# Reach_B0.net
KiCad netlist of a schematic drawn in EAGLE
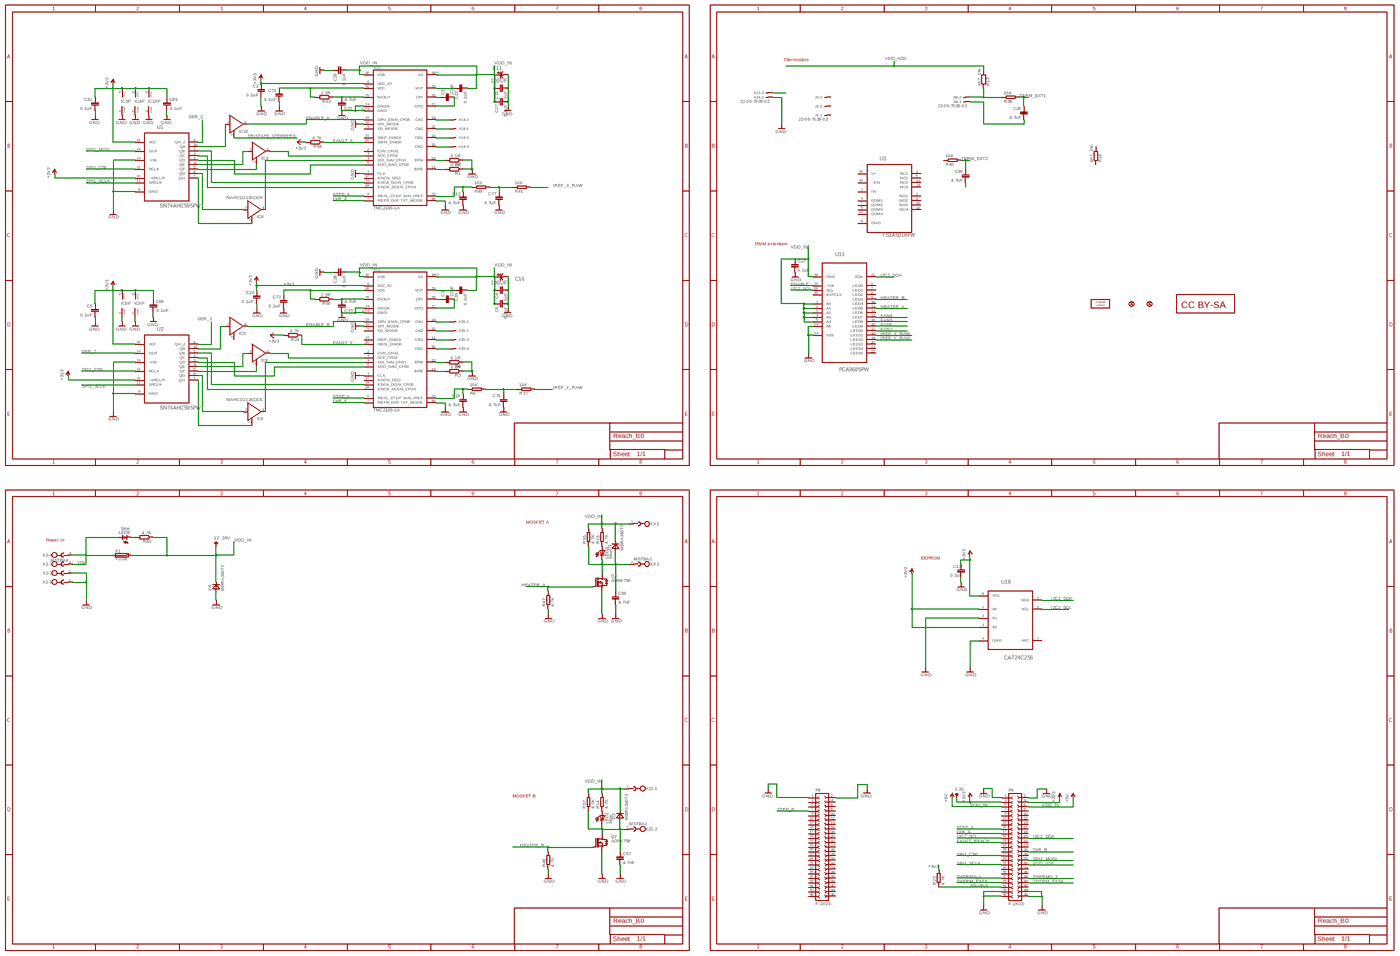
[diagram p0: schematic, sheet 1, overview]
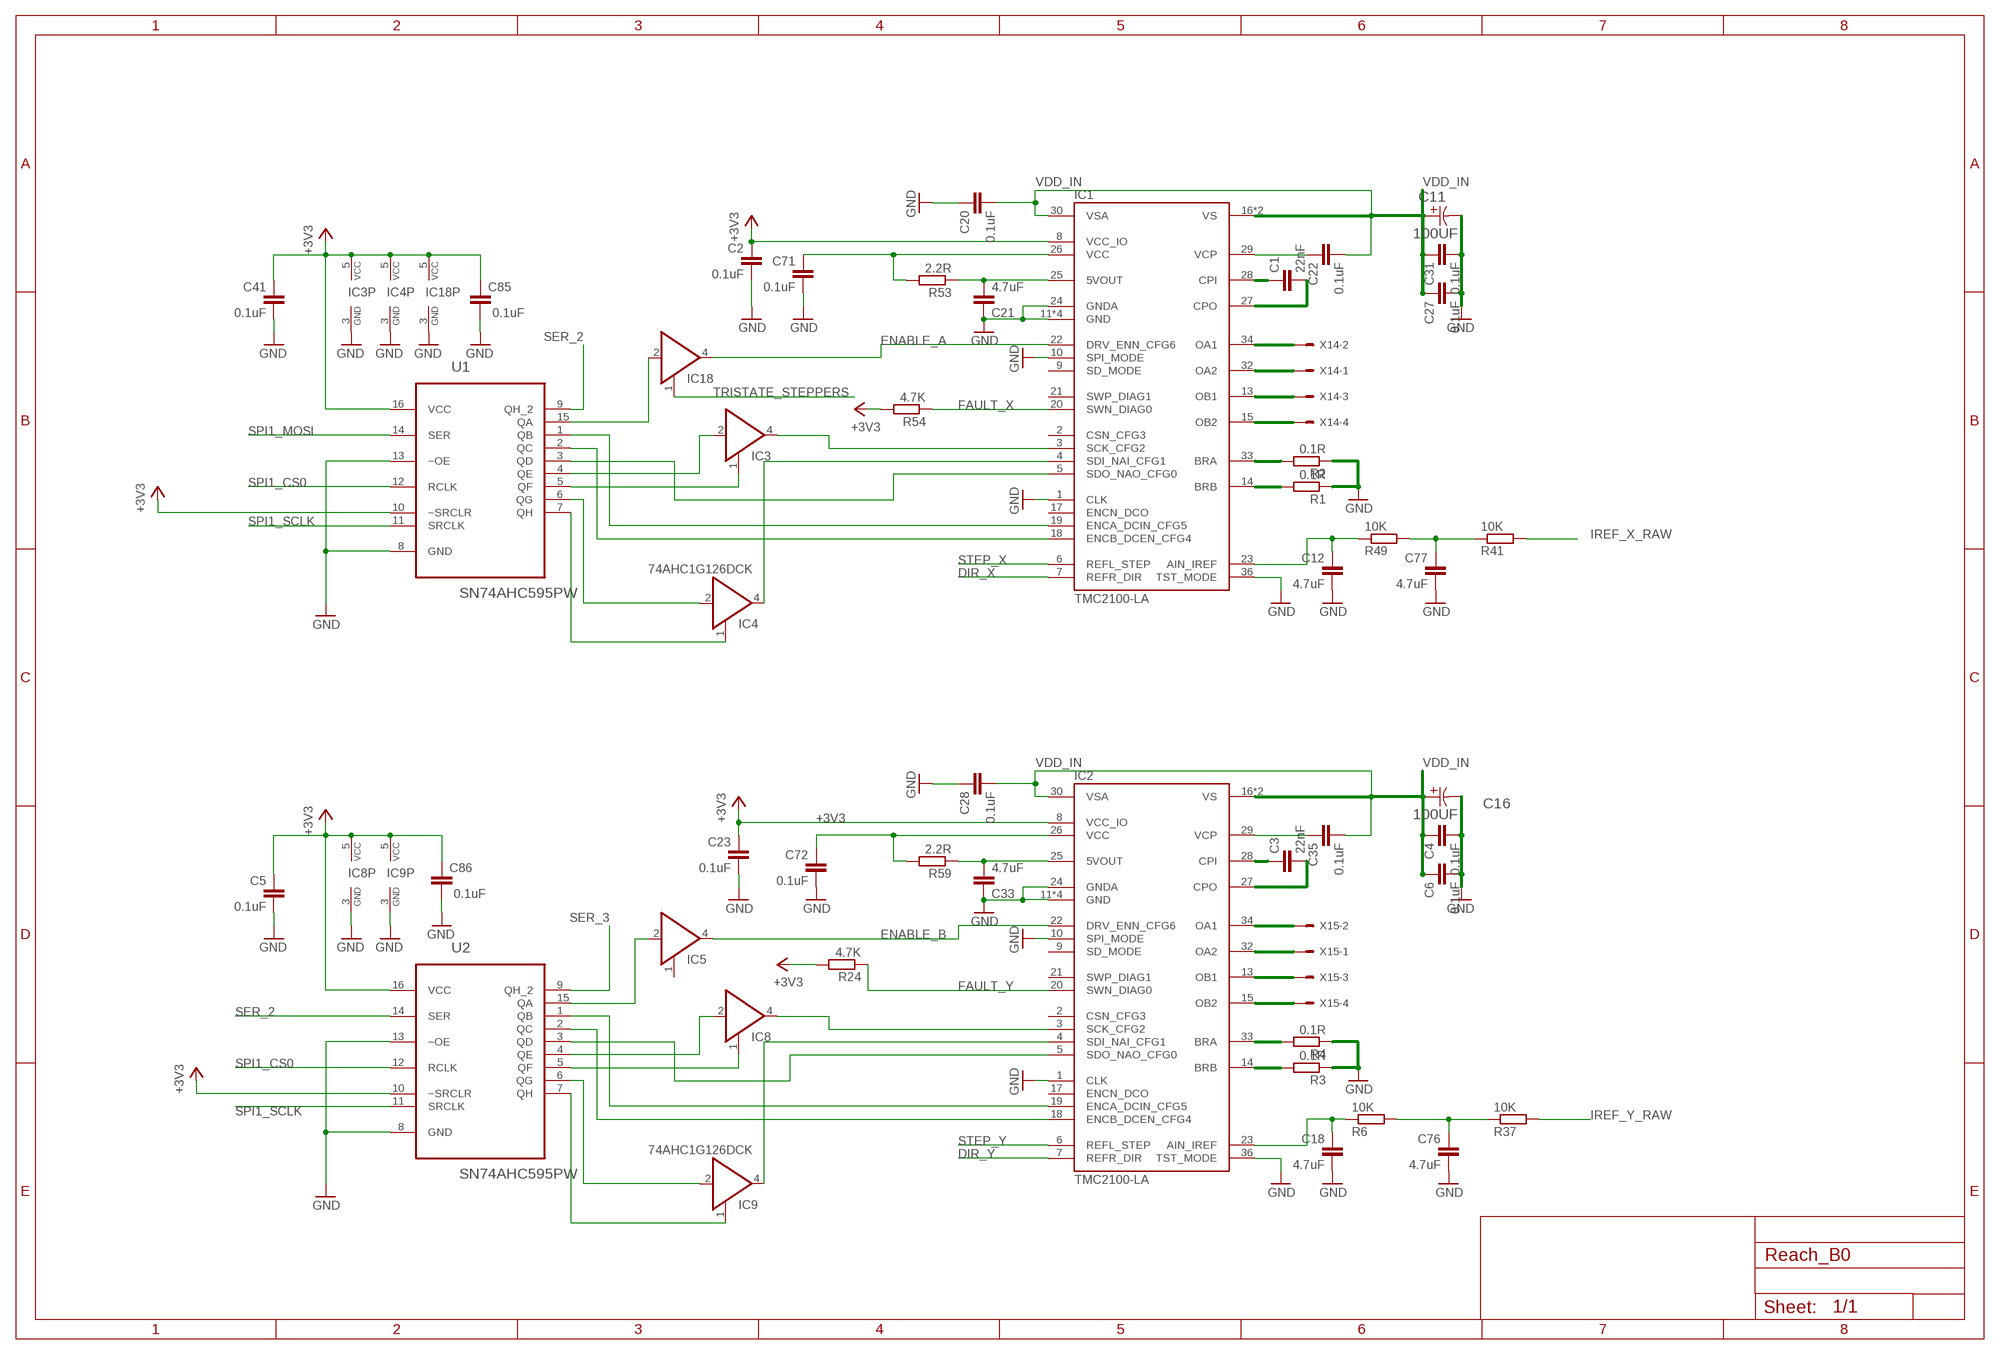
[diagram p1: schematic, sheet 1, part 1 of 4]
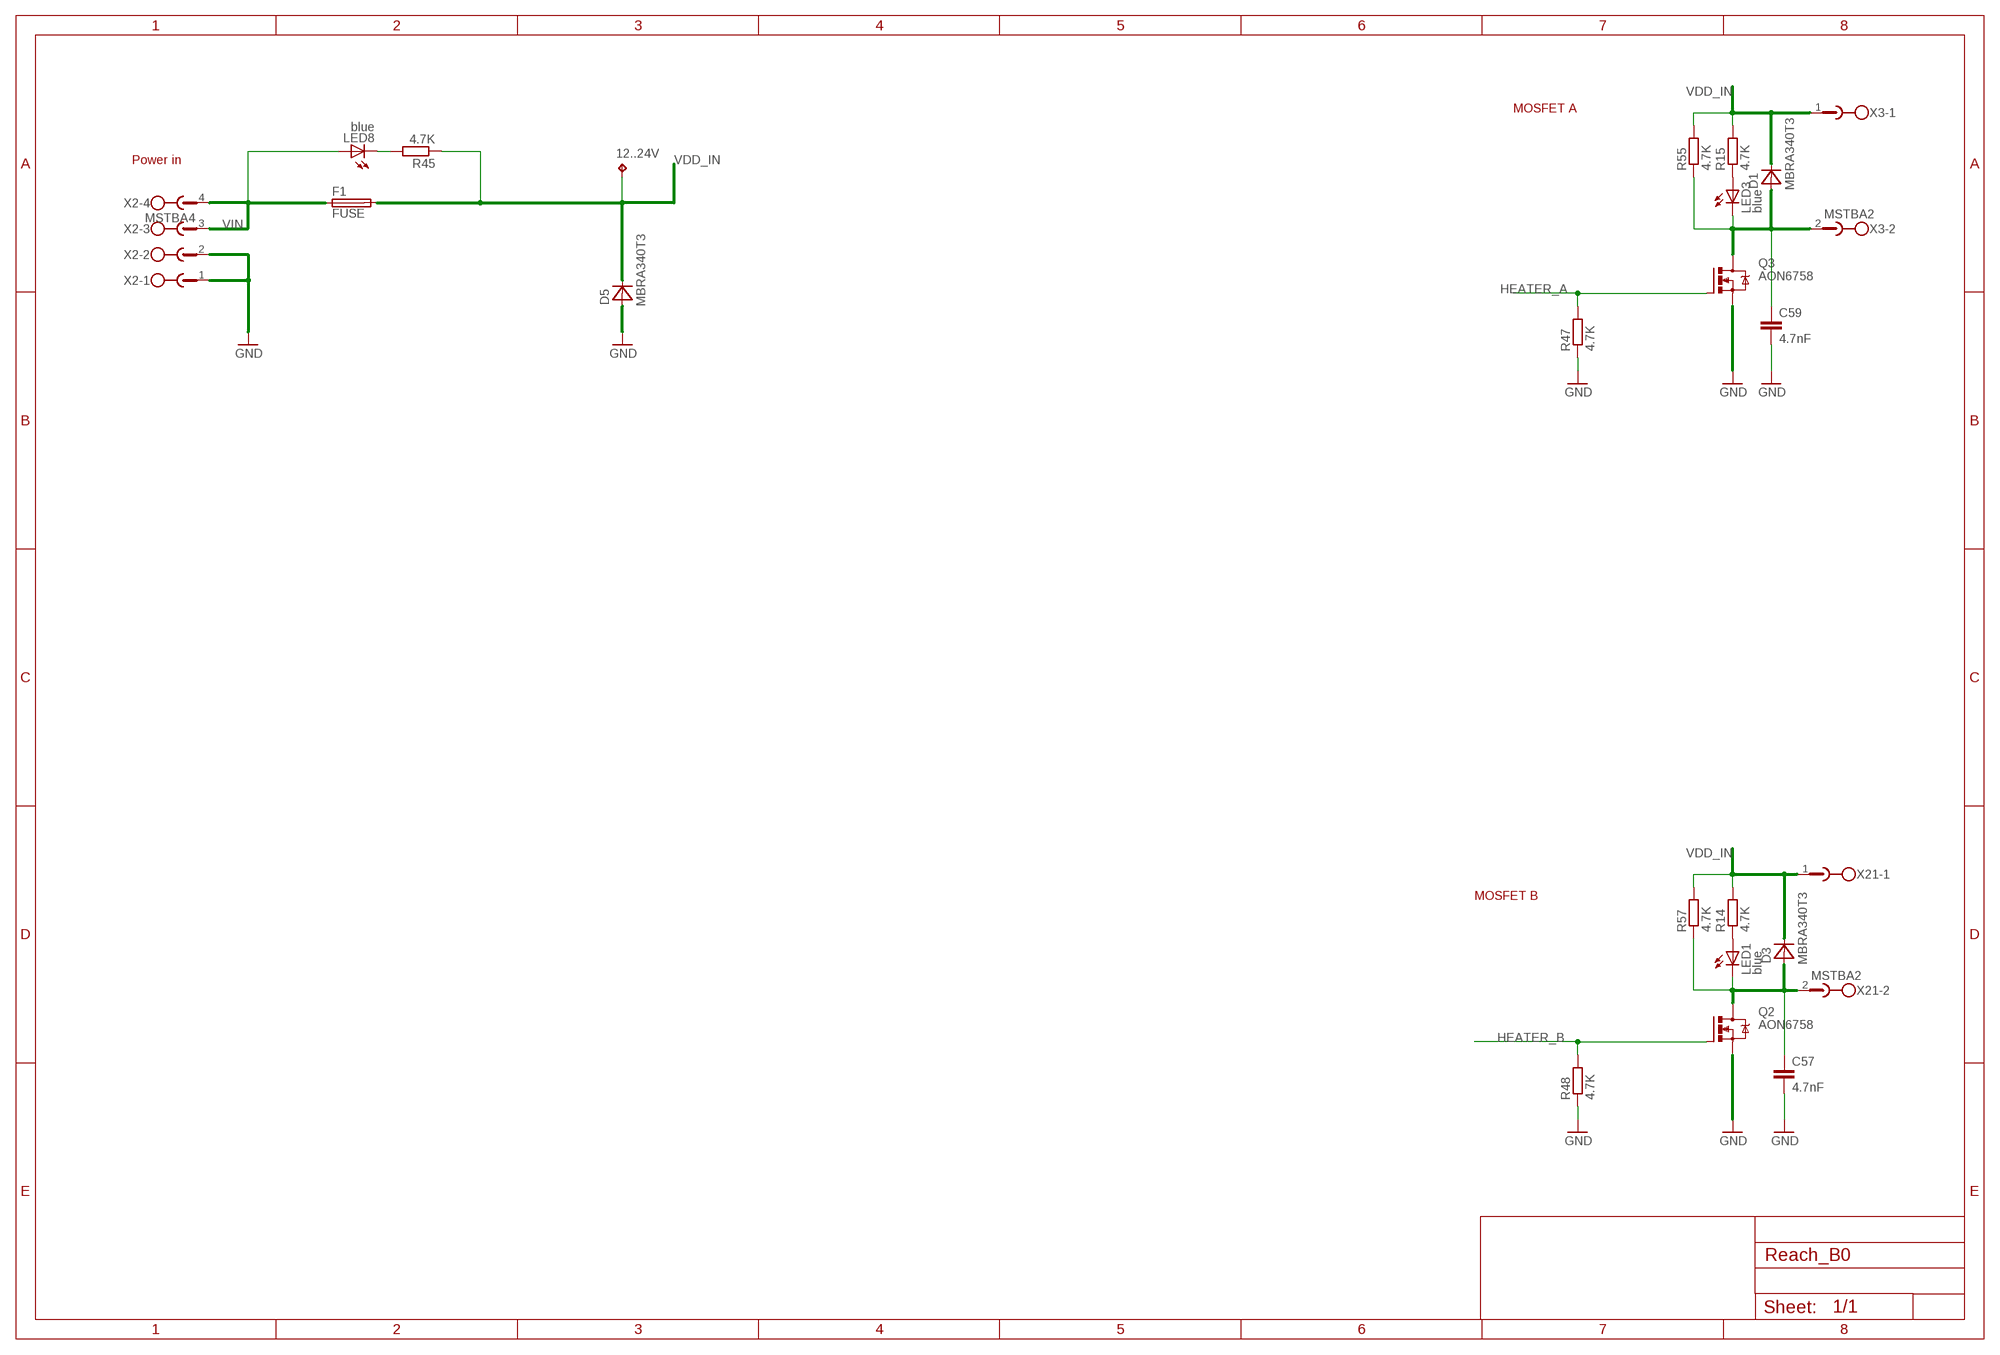
[diagram p2: schematic, sheet 1, part 2 of 4]
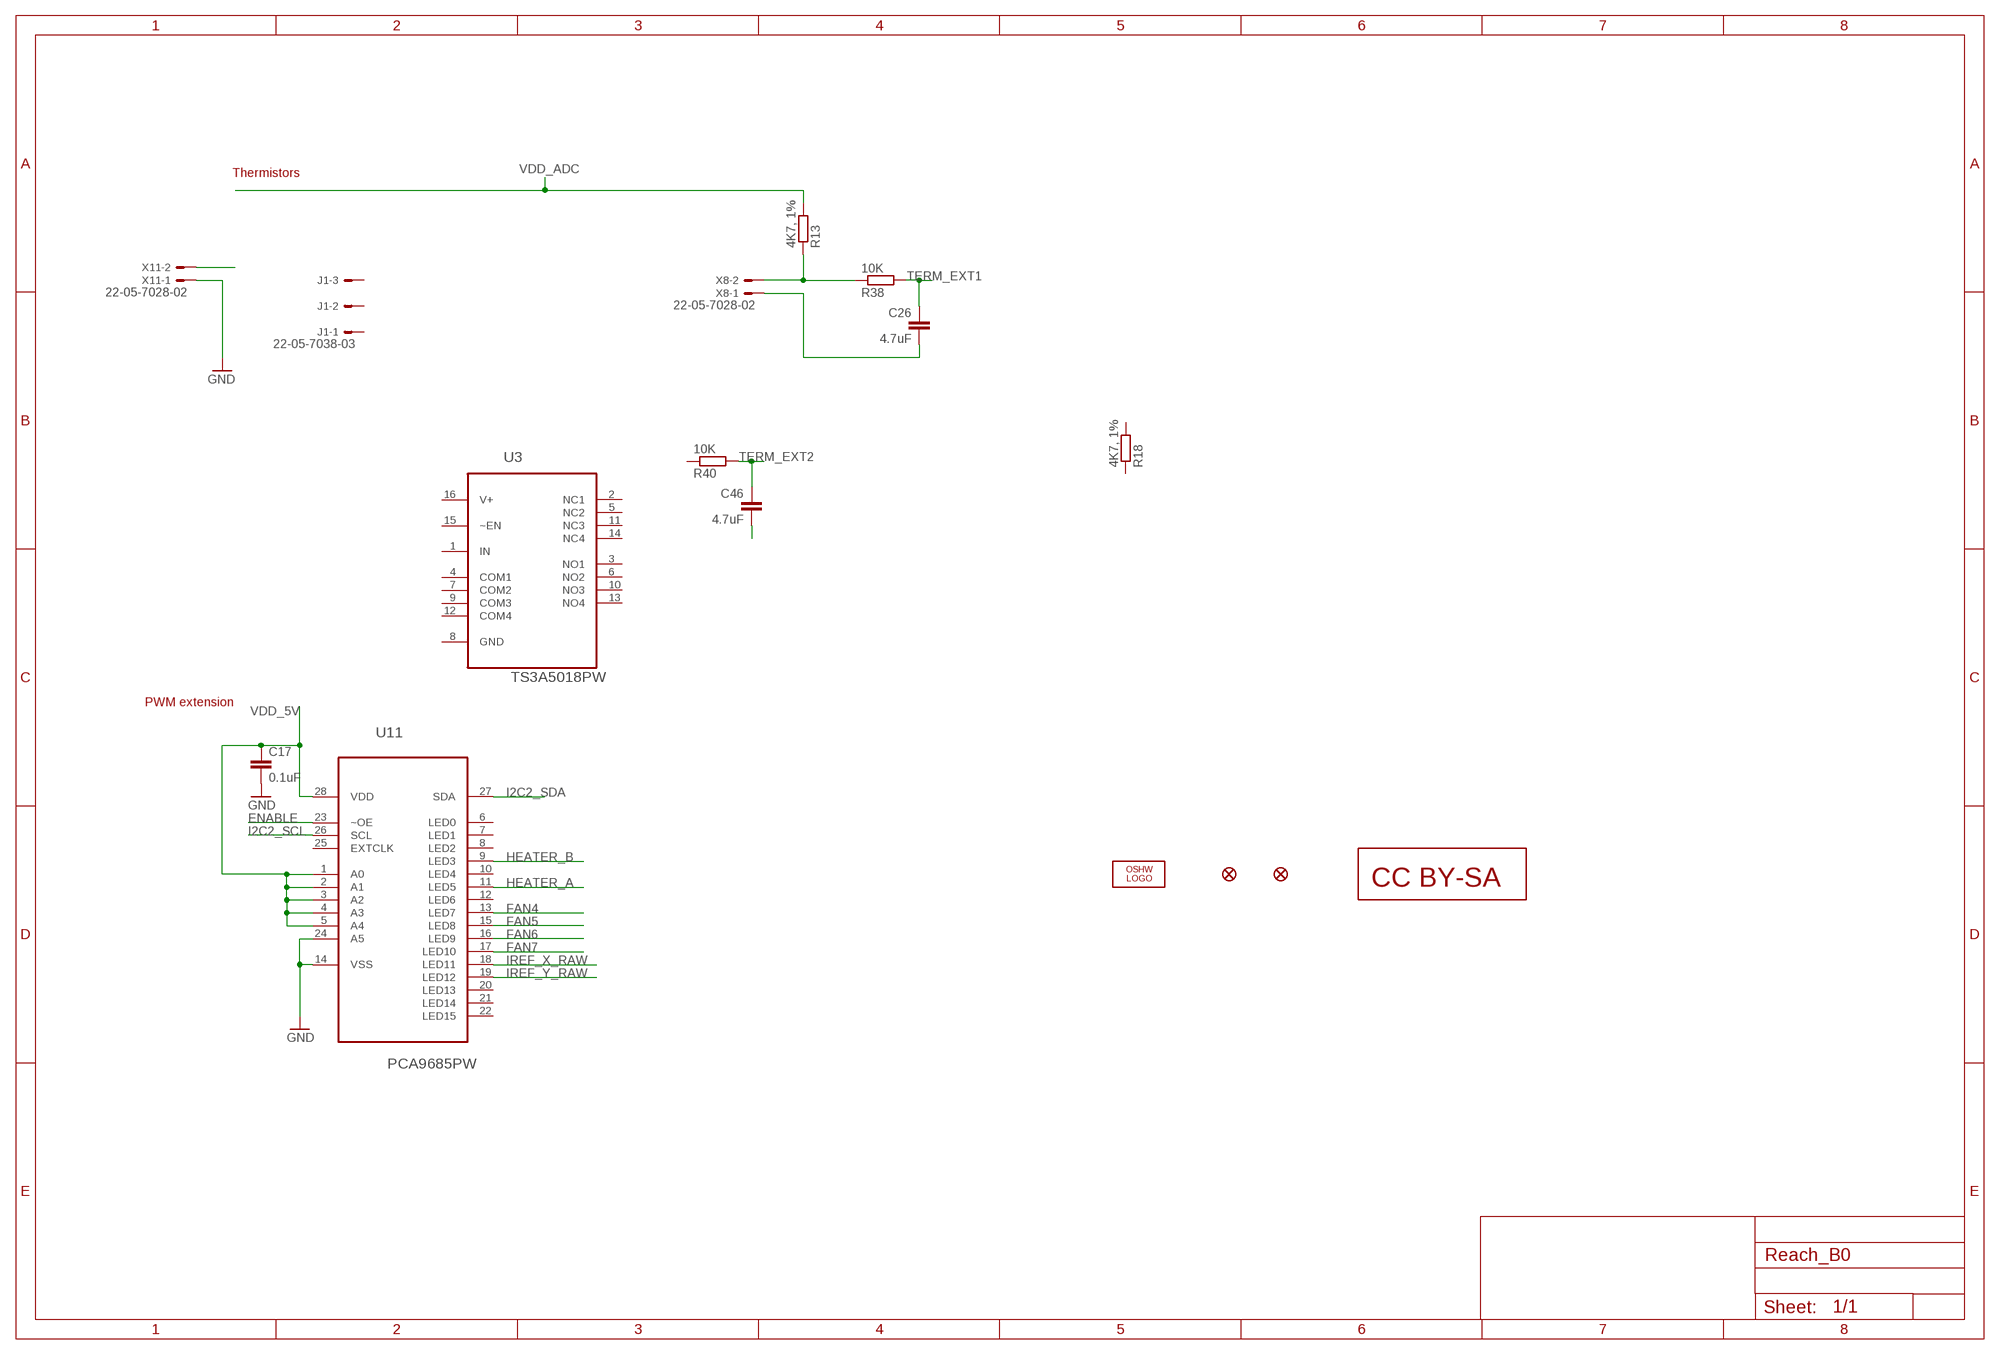
[diagram p3: schematic, sheet 1, part 3 of 4]
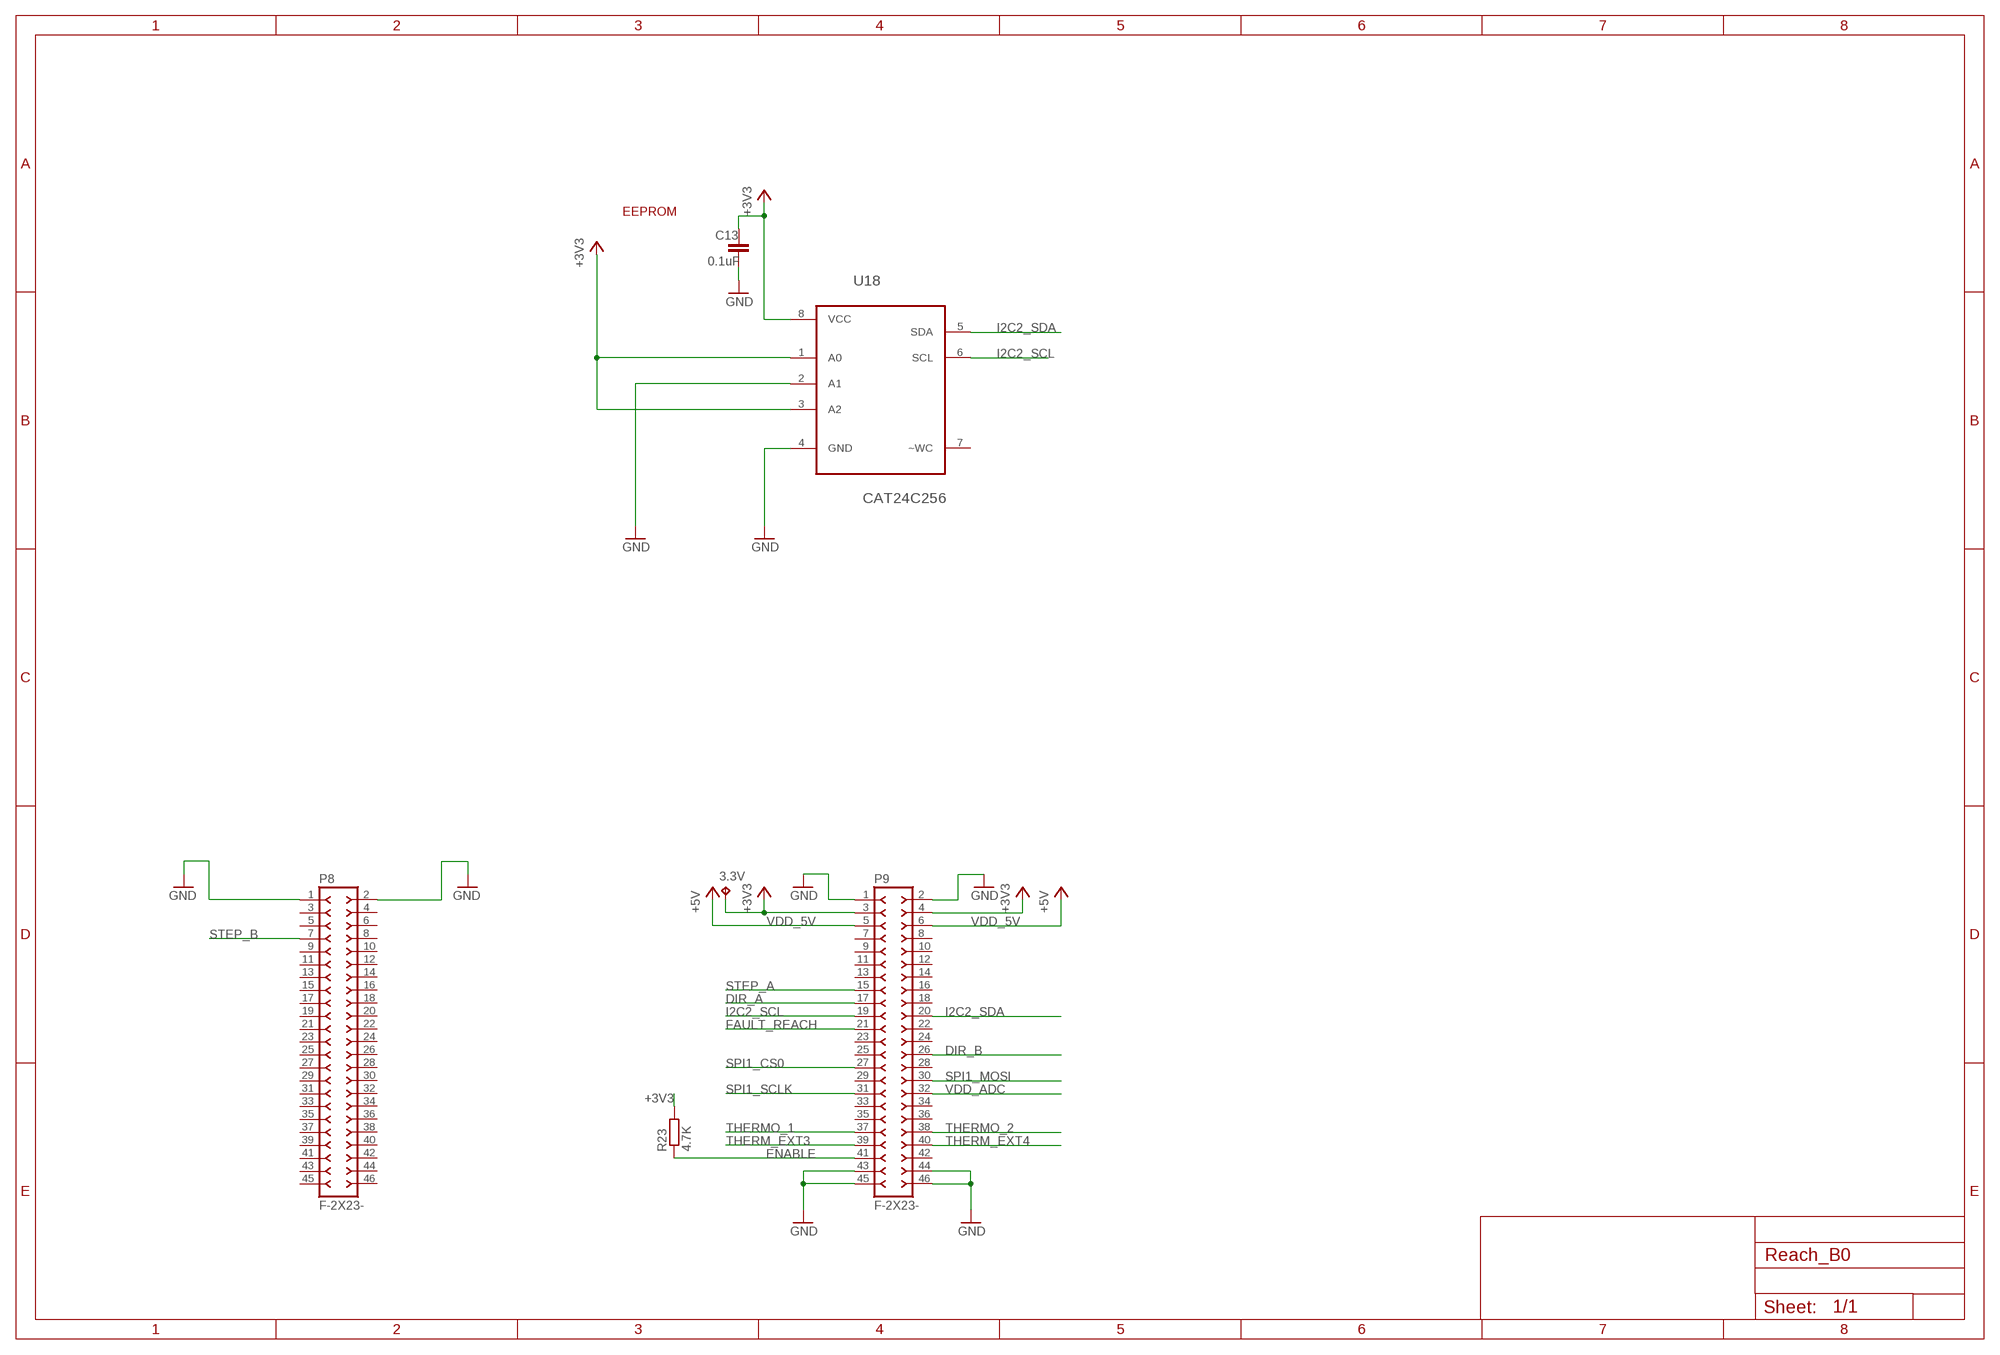
[diagram p4: schematic, sheet 1, part 4 of 4]

(export (version "E")
  (design (tool "Eeschema 10.0.6"))
  (components
    (comp (ref "3.3V")
      (value "TPB1,27")
      (footprint "eagle-import:B1,27")
      (libsource (lib "eagle-import") (part "TPB1,27"))
    )
    (comp (ref "12..24V")
      (value "TPB1,27")
      (footprint "eagle-import:B1,27")
      (libsource (lib "eagle-import") (part "TPB1,27"))
    )
    (comp (ref "C1")
      (value "22nF")
      (footprint "eagle-import:C0402")
      (libsource (lib "eagle-import") (part "C-EUC0402"))
    )
    (comp (ref "C2")
      (value "0.1uF")
      (footprint "eagle-import:C0402")
      (libsource (lib "eagle-import") (part "C-EUC0402"))
    )
    (comp (ref "C3")
      (value "22nF")
      (footprint "eagle-import:C0402")
      (libsource (lib "eagle-import") (part "C-EUC0402"))
    )
    (comp (ref "C4")
      (value "0.1uF")
      (footprint "eagle-import:C0402")
      (libsource (lib "eagle-import") (part "C-EUC0402"))
    )
    (comp (ref "C5")
      (value "0.1uF")
      (footprint "eagle-import:C0402")
      (libsource (lib "eagle-import") (part "C-EUC0402"))
    )
    (comp (ref "C6")
      (value "0.1uF")
      (footprint "eagle-import:C0402")
      (libsource (lib "eagle-import") (part "C-EUC0402"))
    )
    (comp (ref "C11")
      (value "100UF")
      (footprint "eagle-import:CAPAE660X800N")
      (fields (field (name "MPN") "EEE-FK1V101XP") (field (name "TOLERANCE") "±20 %"))
      (libsource (lib "eagle-import") (part "EEE--CASE-D8FK1V101XP"))
    )
    (comp (ref "C12")
      (value "4.7uF")
      (footprint "eagle-import:C0402")
      (libsource (lib "eagle-import") (part "C-EUC0402"))
    )
    (comp (ref "C13")
      (value "0.1uF")
      (footprint "eagle-import:C0402")
      (libsource (lib "eagle-import") (part "C-EUC0402"))
    )
    (comp (ref "C16")
      (value "100UF")
      (footprint "eagle-import:CAPAE660X800N")
      (fields (field (name "MPN") "EEE-FK1V101XP") (field (name "TOLERANCE") "±20 %"))
      (libsource (lib "eagle-import") (part "EEE--CASE-D8FK1V101XP"))
    )
    (comp (ref "C17")
      (value "0.1uF")
      (footprint "eagle-import:C0402")
      (libsource (lib "eagle-import") (part "C-EUC0402"))
    )
    (comp (ref "C18")
      (value "4.7uF")
      (footprint "eagle-import:C0402")
      (libsource (lib "eagle-import") (part "C-EUC0402"))
    )
    (comp (ref "C20")
      (value "0.1uF")
      (footprint "eagle-import:C0402")
      (libsource (lib "eagle-import") (part "C-EUC0402"))
    )
    (comp (ref "C21")
      (value "4.7uF")
      (footprint "eagle-import:C0402")
      (libsource (lib "eagle-import") (part "C-EUC0402"))
    )
    (comp (ref "C22")
      (value "0.1uF")
      (footprint "eagle-import:C0402")
      (libsource (lib "eagle-import") (part "C-EUC0402"))
    )
    (comp (ref "C23")
      (value "0.1uF")
      (footprint "eagle-import:C0402")
      (libsource (lib "eagle-import") (part "C-EUC0402"))
    )
    (comp (ref "C26")
      (value "4.7uF")
      (footprint "eagle-import:C0402")
      (libsource (lib "eagle-import") (part "C-EUC0402"))
    )
    (comp (ref "C27")
      (value "0.1uF")
      (footprint "eagle-import:C0402")
      (libsource (lib "eagle-import") (part "C-EUC0402"))
    )
    (comp (ref "C28")
      (value "0.1uF")
      (footprint "eagle-import:C0402")
      (libsource (lib "eagle-import") (part "C-EUC0402"))
    )
    (comp (ref "C31")
      (value "0.1uF")
      (footprint "eagle-import:C0402")
      (libsource (lib "eagle-import") (part "C-EUC0402"))
    )
    (comp (ref "C33")
      (value "4.7uF")
      (footprint "eagle-import:C0402")
      (libsource (lib "eagle-import") (part "C-EUC0402"))
    )
    (comp (ref "C35")
      (value "0.1uF")
      (footprint "eagle-import:C0402")
      (libsource (lib "eagle-import") (part "C-EUC0402"))
    )
    (comp (ref "C41")
      (value "0.1uF")
      (footprint "eagle-import:C0402")
      (libsource (lib "eagle-import") (part "C-EUC0402"))
    )
    (comp (ref "C46")
      (value "4.7uF")
      (footprint "eagle-import:C0402")
      (libsource (lib "eagle-import") (part "C-EUC0402"))
    )
    (comp (ref "C57")
      (value "4.7nF")
      (footprint "eagle-import:C0402")
      (libsource (lib "eagle-import") (part "C-EUC0402"))
    )
    (comp (ref "C59")
      (value "4.7nF")
      (footprint "eagle-import:C0402")
      (libsource (lib "eagle-import") (part "C-EUC0402"))
    )
    (comp (ref "C71")
      (value "0.1uF")
      (footprint "eagle-import:C0402")
      (libsource (lib "eagle-import") (part "C-EUC0402"))
    )
    (comp (ref "C72")
      (value "0.1uF")
      (footprint "eagle-import:C0402")
      (libsource (lib "eagle-import") (part "C-EUC0402"))
    )
    (comp (ref "C76")
      (value "4.7uF")
      (footprint "eagle-import:C0402")
      (libsource (lib "eagle-import") (part "C-EUC0402"))
    )
    (comp (ref "C77")
      (value "4.7uF")
      (footprint "eagle-import:C0402")
      (libsource (lib "eagle-import") (part "C-EUC0402"))
    )
    (comp (ref "C85")
      (value "0.1uF")
      (footprint "eagle-import:C0402")
      (libsource (lib "eagle-import") (part "C-EUC0402"))
    )
    (comp (ref "C86")
      (value "0.1uF")
      (footprint "eagle-import:C0402")
      (libsource (lib "eagle-import") (part "C-EUC0402"))
    )
    (comp (ref "D1")
      (value "MBRA340T3")
      (footprint "eagle-import:SMA")
      (libsource (lib "eagle-import") (part "MBRA340T3"))
    )
    (comp (ref "D3")
      (value "MBRA340T3")
      (footprint "eagle-import:SMA")
      (libsource (lib "eagle-import") (part "MBRA340T3"))
    )
    (comp (ref "D5")
      (value "MBRA340T3")
      (footprint "eagle-import:SMA")
      (libsource (lib "eagle-import") (part "MBRA340T3"))
    )
    (comp (ref "F1")
      (value "FUSE")
      (footprint "eagle-import:3557")
      (libsource (lib "eagle-import") (part "FUSE"))
    )
    (comp (ref "IC1")
      (value "TMC2100-LA")
      (footprint "eagle-import:QFN36-PAD")
      (libsource (lib "eagle-import") (part "TMC2100-LA"))
    )
    (comp (ref "IC2")
      (value "TMC2100-LA")
      (footprint "eagle-import:QFN36-PAD")
      (libsource (lib "eagle-import") (part "TMC2100-LA"))
    )
    (comp (ref "IC3")
      (value "74AHC1G126DCK")
      (footprint "eagle-import:SC70-5")
      (libsource (lib "eagle-import") (part "741G126DCKAHC"))
    )
    (comp (ref "IC4")
      (value "74AHC1G126DCK")
      (footprint "eagle-import:SC70-5")
      (libsource (lib "eagle-import") (part "741G126DCKAHC"))
    )
    (comp (ref "IC5")
      (value "74AHC1G126DCK")
      (footprint "eagle-import:SC70-5")
      (libsource (lib "eagle-import") (part "741G126DCKAHC"))
    )
    (comp (ref "IC8")
      (value "74AHC1G126DCK")
      (footprint "eagle-import:SC70-5")
      (libsource (lib "eagle-import") (part "741G126DCKAHC"))
    )
    (comp (ref "IC9")
      (value "74AHC1G126DCK")
      (footprint "eagle-import:SC70-5")
      (libsource (lib "eagle-import") (part "741G126DCKAHC"))
    )
    (comp (ref "IC18")
      (value "74AHC1G126DCK")
      (footprint "eagle-import:SC70-5")
      (libsource (lib "eagle-import") (part "741G126DCKAHC"))
    )
    (comp (ref "J1")
      (value "22-05-7038-03")
      (footprint "eagle-import:7395-03")
      (libsource (lib "eagle-import") (part "22-?-0305-7038"))
    )
    (comp (ref "JP1")
      (value "FIDUCIAL1X2.5")
      (footprint "eagle-import:FIDUCIAL-1X2.5")
      (libsource (lib "eagle-import") (part "FIDUCIAL1X2.5"))
    )
    (comp (ref "JP2")
      (value "FIDUCIAL1X2.5")
      (footprint "eagle-import:FIDUCIAL-1X2.5")
      (libsource (lib "eagle-import") (part "FIDUCIAL1X2.5"))
    )
    (comp (ref "LED1")
      (value "blue")
      (footprint "eagle-import:CHIP-LED0603")
      (libsource (lib "eagle-import") (part "LEDCHIP-LED0603"))
    )
    (comp (ref "LED3")
      (value "blue")
      (footprint "eagle-import:CHIP-LED0603")
      (libsource (lib "eagle-import") (part "LEDCHIP-LED0603"))
    )
    (comp (ref "LED8")
      (value "blue")
      (footprint "eagle-import:CHIP-LED0603")
      (libsource (lib "eagle-import") (part "LEDCHIP-LED0603"))
    )
    (comp (ref "LOGO1")
      (value "OSHW_LOGO_FILLX0200-NT")
      (footprint "eagle-import:OSHW_FILLX200_NOTEXT")
      (libsource (lib "eagle-import") (part "OSHW_LOGO_FILLX0200-NT"))
    )
    (comp (ref "P8")
      (value "F-2X23-")
      (footprint "eagle-import:DIL-100-2X23")
      (libsource (lib "eagle-import") (part "F-2X23-"))
    )
    (comp (ref "P9")
      (value "F-2X23-")
      (footprint "eagle-import:DIL-100-2X23")
      (libsource (lib "eagle-import") (part "F-2X23-"))
    )
    (comp (ref "Q2")
      (value "AON6758")
      (footprint "eagle-import:8-DFN-EP-(5X6)")
      (libsource (lib "eagle-import") (part "AON6758"))
    )
    (comp (ref "Q3")
      (value "AON6758")
      (footprint "eagle-import:8-DFN-EP-(5X6)")
      (libsource (lib "eagle-import") (part "AON6758"))
    )
    (comp (ref "R1")
      (value "0.1R")
      (footprint "eagle-import:R0805")
      (libsource (lib "eagle-import") (part "R-EU_R0805"))
    )
    (comp (ref "R2")
      (value "0.1R")
      (footprint "eagle-import:R0805")
      (libsource (lib "eagle-import") (part "R-EU_R0805"))
    )
    (comp (ref "R3")
      (value "0.1R")
      (footprint "eagle-import:R0805")
      (libsource (lib "eagle-import") (part "R-EU_R0805"))
    )
    (comp (ref "R4")
      (value "0.1R")
      (footprint "eagle-import:R0805")
      (libsource (lib "eagle-import") (part "R-EU_R0805"))
    )
    (comp (ref "R6")
      (value "10K")
      (footprint "eagle-import:R0402")
      (libsource (lib "eagle-import") (part "R-EU_R0402"))
    )
    (comp (ref "R13")
      (value "4K7, 1%")
      (footprint "eagle-import:R0402")
      (libsource (lib "eagle-import") (part "R-EU_R0402"))
    )
    (comp (ref "R14")
      (value "4.7K")
      (footprint "eagle-import:R0402")
      (libsource (lib "eagle-import") (part "R-EU_R0402"))
    )
    (comp (ref "R15")
      (value "4.7K")
      (footprint "eagle-import:R0402")
      (libsource (lib "eagle-import") (part "R-EU_R0402"))
    )
    (comp (ref "R18")
      (value "4K7, 1%")
      (footprint "eagle-import:R0402")
      (libsource (lib "eagle-import") (part "R-EU_R0402"))
    )
    (comp (ref "R23")
      (value "4.7K")
      (footprint "eagle-import:R0402")
      (libsource (lib "eagle-import") (part "R-EU_R0402"))
    )
    (comp (ref "R24")
      (value "4.7K")
      (footprint "eagle-import:R0402")
      (libsource (lib "eagle-import") (part "R-EU_R0402"))
    )
    (comp (ref "R37")
      (value "10K")
      (footprint "eagle-import:R0402")
      (libsource (lib "eagle-import") (part "R-EU_R0402"))
    )
    (comp (ref "R38")
      (value "10K")
      (footprint "eagle-import:R0402")
      (libsource (lib "eagle-import") (part "R-EU_R0402"))
    )
    (comp (ref "R40")
      (value "10K")
      (footprint "eagle-import:R0402")
      (libsource (lib "eagle-import") (part "R-EU_R0402"))
    )
    (comp (ref "R41")
      (value "10K")
      (footprint "eagle-import:R0402")
      (libsource (lib "eagle-import") (part "R-EU_R0402"))
    )
    (comp (ref "R45")
      (value "4.7K")
      (footprint "eagle-import:R0402")
      (libsource (lib "eagle-import") (part "R-EU_R0402"))
    )
    (comp (ref "R47")
      (value "4.7K")
      (footprint "eagle-import:R0402")
      (libsource (lib "eagle-import") (part "R-EU_R0402"))
    )
    (comp (ref "R48")
      (value "4.7K")
      (footprint "eagle-import:R0402")
      (libsource (lib "eagle-import") (part "R-EU_R0402"))
    )
    (comp (ref "R49")
      (value "10K")
      (footprint "eagle-import:R0402")
      (libsource (lib "eagle-import") (part "R-EU_R0402"))
    )
    (comp (ref "R53")
      (value "2.2R")
      (footprint "eagle-import:R0402")
      (libsource (lib "eagle-import") (part "R-EU_R0402"))
    )
    (comp (ref "R54")
      (value "4.7K")
      (footprint "eagle-import:R0402")
      (libsource (lib "eagle-import") (part "R-EU_R0402"))
    )
    (comp (ref "R55")
      (value "4.7K")
      (footprint "eagle-import:R0402")
      (libsource (lib "eagle-import") (part "R-EU_R0402"))
    )
    (comp (ref "R57")
      (value "4.7K")
      (footprint "eagle-import:R0402")
      (libsource (lib "eagle-import") (part "R-EU_R0402"))
    )
    (comp (ref "R59")
      (value "2.2R")
      (footprint "eagle-import:R0402")
      (libsource (lib "eagle-import") (part "R-EU_R0402"))
    )
    (comp (ref "U$4")
      (value "CC-BY-SA")
      (footprint "eagle-import:CC-BY-SA")
      (libsource (lib "eagle-import") (part "CC-BY-SA"))
    )
    (comp (ref "U1")
      (value "SN74AHC595PW")
      (footprint "eagle-import:SOP65P640X120-16N")
      (libsource (lib "eagle-import") (part "SN74AHC595PW"))
    )
    (comp (ref "U2")
      (value "SN74AHC595PW")
      (footprint "eagle-import:SOP65P640X120-16N")
      (libsource (lib "eagle-import") (part "SN74AHC595PW"))
    )
    (comp (ref "U3")
      (value "TS3A5018PW")
      (footprint "eagle-import:SOP65P640X120-16N")
      (libsource (lib "eagle-import") (part "TS3A5018PW"))
    )
    (comp (ref "U11")
      (value "PCA9685PW")
      (footprint "eagle-import:SOP65P640X110-28N")
      (libsource (lib "eagle-import") (part "PCA9685PW"))
    )
    (comp (ref "U18")
      (value "CAT24C256")
      (footprint "eagle-import:SOIC127P600X175-8N")
      (libsource (lib "eagle-import") (part "CAT24C256"))
    )
    (comp (ref "X2")
      (value "MSTBA4")
      (footprint "eagle-import:MSTBA4")
      (fields (field (name "MF") "FARNELL") (field (name "MPN") "1757268"))
      (libsource (lib "eagle-import") (part "MSTBA4"))
    )
    (comp (ref "X3")
      (value "MSTBA2")
      (footprint "eagle-import:MSTBA2")
      (fields (field (name "MF") "FARNELL") (field (name "MPN") "1757242"))
      (libsource (lib "eagle-import") (part "MSTBA2"))
    )
    (comp (ref "X8")
      (value "22-05-7028-02")
      (footprint "eagle-import:7395-02")
      (libsource (lib "eagle-import") (part "22-?-0205-7028"))
    )
    (comp (ref "X11")
      (value "22-05-7028-02")
      (footprint "eagle-import:7395-02")
      (libsource (lib "eagle-import") (part "22-?-0205-7028"))
    )
    (comp (ref "X14")
      (value "22-05-7048-04")
      (footprint "eagle-import:7395-04")
      (libsource (lib "eagle-import") (part "22-?-0405-7048"))
    )
    (comp (ref "X15")
      (value "22-05-7048-04")
      (footprint "eagle-import:7395-04")
      (libsource (lib "eagle-import") (part "22-?-0405-7048"))
    )
    (comp (ref "X21")
      (value "MSTBA2")
      (footprint "eagle-import:MSTBA2")
      (fields (field (name "MF") "FARNELL") (field (name "MPN") "1757242"))
      (libsource (lib "eagle-import") (part "MSTBA2"))
    )
  )
  (nets
    (net (code "1") (name "+3V3") (class "Default")
      (node (ref "3.3V") (pin "TP") (pinfunction "TP_TP") (pintype "input"))
      (node (ref "C13") (pin "1") (pinfunction "1_1") (pintype "passive"))
      (node (ref "C2") (pin "1") (pinfunction "1_1") (pintype "passive"))
      (node (ref "C23") (pin "1") (pinfunction "1_1") (pintype "passive"))
      (node (ref "C41") (pin "1") (pinfunction "1_1") (pintype "passive"))
      (node (ref "C5") (pin "1") (pinfunction "1_1") (pintype "passive"))
      (node (ref "C85") (pin "1") (pinfunction "1_1") (pintype "passive"))
      (node (ref "C86") (pin "1") (pinfunction "1_1") (pintype "passive"))
      (node (ref "IC1") (pin "8") (pinfunction "VCC_IO_8") (pintype "bidirectional"))
      (node (ref "IC18") (pin "5") (pinfunction "VCC_5") (pintype "power_in"))
      (node (ref "IC2") (pin "8") (pinfunction "VCC_IO_8") (pintype "bidirectional"))
      (node (ref "IC3") (pin "5") (pinfunction "VCC_5") (pintype "power_in"))
      (node (ref "IC4") (pin "5") (pinfunction "VCC_5") (pintype "power_in"))
      (node (ref "IC8") (pin "5") (pinfunction "VCC_5") (pintype "power_in"))
      (node (ref "IC9") (pin "5") (pinfunction "VCC_5") (pintype "power_in"))
      (node (ref "P9") (pin "3") (pinfunction "3_3") (pintype "passive"))
      (node (ref "P9") (pin "4") (pinfunction "4_4") (pintype "passive"))
      (node (ref "R23") (pin "2") (pinfunction "2_2") (pintype "passive"))
      (node (ref "R24") (pin "2") (pinfunction "2_2") (pintype "passive"))
      (node (ref "R54") (pin "2") (pinfunction "2_2") (pintype "passive"))
      (node (ref "U1") (pin "10") (pinfunction "~{SRCLR}_10") (pintype "input"))
      (node (ref "U1") (pin "16") (pinfunction "VCC_16") (pintype "power_in"))
      (node (ref "U18") (pin "1") (pinfunction "A0_1") (pintype "input"))
      (node (ref "U18") (pin "3") (pinfunction "A2_3") (pintype "input"))
      (node (ref "U18") (pin "8") (pinfunction "VCC_8") (pintype "power_in"))
      (node (ref "U2") (pin "10") (pinfunction "~{SRCLR}_10") (pintype "input"))
      (node (ref "U2") (pin "16") (pinfunction "VCC_16") (pintype "power_in"))
    )
    (net (code "2") (name "+5V") (class "Default")
      (node (ref "C17") (pin "1") (pinfunction "1_1") (pintype "passive"))
      (node (ref "P9") (pin "5") (pinfunction "5_5") (pintype "passive"))
      (node (ref "P9") (pin "6") (pinfunction "6_6") (pintype "passive"))
      (node (ref "U11") (pin "1") (pinfunction "A0_1") (pintype "input"))
      (node (ref "U11") (pin "2") (pinfunction "A1_2") (pintype "input"))
      (node (ref "U11") (pin "28") (pinfunction "VDD_28") (pintype "power_in"))
      (node (ref "U11") (pin "3") (pinfunction "A2_3") (pintype "input"))
      (node (ref "U11") (pin "4") (pinfunction "A3_4") (pintype "input"))
      (node (ref "U11") (pin "5") (pinfunction "A4_5") (pintype "input"))
    )
    (net (code "3") (name "/DIR_A") (class "Default")
      (node (ref "P9") (pin "17") (pinfunction "17_17") (pintype "passive"))
    )
    (net (code "4") (name "/DIR_B") (class "Default")
      (node (ref "P9") (pin "26") (pinfunction "26_26") (pintype "passive"))
    )
    (net (code "5") (name "/DIR_X") (class "Default")
      (node (ref "IC1") (pin "7") (pinfunction "REFR_DIR_7") (pintype "bidirectional"))
    )
    (net (code "6") (name "/DIR_Y") (class "Default")
      (node (ref "IC2") (pin "7") (pinfunction "REFR_DIR_7") (pintype "bidirectional"))
    )
    (net (code "7") (name "/ENABLE") (class "Default")
      (node (ref "P9") (pin "41") (pinfunction "41_41") (pintype "passive"))
      (node (ref "R23") (pin "1") (pinfunction "1_1") (pintype "passive"))
      (node (ref "U11") (pin "23") (pinfunction "~{OE}_23") (pintype "input"))
    )
    (net (code "8") (name "/ENABLE_A") (class "Default")
      (node (ref "IC1") (pin "22") (pinfunction "DRV_ENN_CFG6_22") (pintype "bidirectional"))
      (node (ref "IC18") (pin "4") (pinfunction "O_4") (pintype "output"))
    )
    (net (code "9") (name "/ENABLE_B") (class "Default")
      (node (ref "IC2") (pin "22") (pinfunction "DRV_ENN_CFG6_22") (pintype "bidirectional"))
      (node (ref "IC5") (pin "4") (pinfunction "O_4") (pintype "output"))
    )
    (net (code "10") (name "/FAN4") (class "Default")
      (node (ref "U11") (pin "13") (pinfunction "LED7_13") (pintype "output"))
    )
    (net (code "11") (name "/FAN5") (class "Default")
      (node (ref "U11") (pin "15") (pinfunction "LED8_15") (pintype "output"))
    )
    (net (code "12") (name "/FAN6") (class "Default")
      (node (ref "U11") (pin "16") (pinfunction "LED9_16") (pintype "output"))
    )
    (net (code "13") (name "/FAN7") (class "Default")
      (node (ref "U11") (pin "17") (pinfunction "LED10_17") (pintype "output"))
    )
    (net (code "14") (name "/FAULT_REACH") (class "Default")
      (node (ref "P9") (pin "21") (pinfunction "21_21") (pintype "passive"))
    )
    (net (code "15") (name "/FAULT_X") (class "Default")
      (node (ref "IC1") (pin "20") (pinfunction "SWN_DIAG0_20") (pintype "bidirectional"))
      (node (ref "R54") (pin "1") (pinfunction "1_1") (pintype "passive"))
    )
    (net (code "16") (name "/FAULT_Y") (class "Default")
      (node (ref "IC2") (pin "20") (pinfunction "SWN_DIAG0_20") (pintype "bidirectional"))
      (node (ref "R24") (pin "1") (pinfunction "1_1") (pintype "passive"))
    )
    (net (code "17") (name "/HEATER_A") (class "Default")
      (node (ref "Q3") (pin "4") (pinfunction "G_4") (pintype "passive"))
      (node (ref "R47") (pin "2") (pinfunction "2_2") (pintype "passive"))
      (node (ref "U11") (pin "11") (pinfunction "LED5_11") (pintype "output"))
    )
    (net (code "18") (name "/HEATER_B") (class "Default")
      (node (ref "Q2") (pin "4") (pinfunction "G_4") (pintype "passive"))
      (node (ref "R48") (pin "2") (pinfunction "2_2") (pintype "passive"))
      (node (ref "U11") (pin "9") (pinfunction "LED3_9") (pintype "output"))
    )
    (net (code "19") (name "/I2C2_SCL") (class "Default")
      (node (ref "P9") (pin "19") (pinfunction "19_19") (pintype "passive"))
      (node (ref "U11") (pin "26") (pinfunction "SCL_26") (pintype "input"))
      (node (ref "U18") (pin "6") (pinfunction "SCL_6") (pintype "input"))
    )
    (net (code "20") (name "/I2C2_SDA") (class "Default")
      (node (ref "P9") (pin "20") (pinfunction "20_20") (pintype "passive"))
      (node (ref "U11") (pin "27") (pinfunction "SDA_27") (pintype "bidirectional"))
      (node (ref "U18") (pin "5") (pinfunction "SDA_5") (pintype "bidirectional"))
    )
    (net (code "21") (name "/IREF_X_RAW") (class "Default")
      (node (ref "R41") (pin "2") (pinfunction "2_2") (pintype "passive"))
      (node (ref "U11") (pin "18") (pinfunction "LED11_18") (pintype "output"))
    )
    (net (code "22") (name "/IREF_Y_RAW") (class "Default")
      (node (ref "R37") (pin "2") (pinfunction "2_2") (pintype "passive"))
      (node (ref "U11") (pin "19") (pinfunction "LED12_19") (pintype "output"))
    )
    (net (code "23") (name "/SER_2") (class "Default")
      (node (ref "U1") (pin "9") (pinfunction "QH_2_9") (pintype "output"))
      (node (ref "U2") (pin "14") (pinfunction "SER_14") (pintype "input"))
    )
    (net (code "24") (name "/SER_3") (class "Default")
      (node (ref "U2") (pin "9") (pinfunction "QH_2_9") (pintype "output"))
    )
    (net (code "25") (name "/SPI1_CS0") (class "Default")
      (node (ref "P9") (pin "27") (pinfunction "27_27") (pintype "passive"))
      (node (ref "U1") (pin "12") (pinfunction "RCLK_12") (pintype "input"))
      (node (ref "U2") (pin "12") (pinfunction "RCLK_12") (pintype "input"))
    )
    (net (code "26") (name "/SPI1_MOSI") (class "Default")
      (node (ref "P9") (pin "30") (pinfunction "30_30") (pintype "passive"))
      (node (ref "U1") (pin "14") (pinfunction "SER_14") (pintype "input"))
    )
    (net (code "27") (name "/SPI1_SCLK") (class "Default")
      (node (ref "P9") (pin "31") (pinfunction "31_31") (pintype "passive"))
      (node (ref "U1") (pin "11") (pinfunction "SRCLK_11") (pintype "input"))
      (node (ref "U2") (pin "11") (pinfunction "SRCLK_11") (pintype "input"))
    )
    (net (code "28") (name "/STEP_A") (class "Default")
      (node (ref "P9") (pin "15") (pinfunction "15_15") (pintype "passive"))
    )
    (net (code "29") (name "/STEP_B") (class "Default")
      (node (ref "P8") (pin "7") (pinfunction "7_7") (pintype "passive"))
    )
    (net (code "30") (name "/STEP_X") (class "Default")
      (node (ref "IC1") (pin "6") (pinfunction "REFL_STEP_6") (pintype "bidirectional"))
    )
    (net (code "31") (name "/STEP_Y") (class "Default")
      (node (ref "IC2") (pin "6") (pinfunction "REFL_STEP_6") (pintype "bidirectional"))
    )
    (net (code "32") (name "/TERM_EXT1") (class "Default")
      (node (ref "C26") (pin "1") (pinfunction "1_1") (pintype "passive"))
      (node (ref "R38") (pin "2") (pinfunction "2_2") (pintype "passive"))
    )
    (net (code "33") (name "/TERM_EXT2") (class "Default")
      (node (ref "C46") (pin "1") (pinfunction "1_1") (pintype "passive"))
      (node (ref "R40") (pin "2") (pinfunction "2_2") (pintype "passive"))
    )
    (net (code "34") (name "/THERMO_1") (class "Default")
      (node (ref "P9") (pin "37") (pinfunction "37_37") (pintype "passive"))
    )
    (net (code "35") (name "/THERMO_2") (class "Default")
      (node (ref "P9") (pin "38") (pinfunction "38_38") (pintype "passive"))
    )
    (net (code "36") (name "/THERM_EXT3") (class "Default")
      (node (ref "P9") (pin "39") (pinfunction "39_39") (pintype "passive"))
    )
    (net (code "37") (name "/THERM_EXT4") (class "Default")
      (node (ref "P9") (pin "40") (pinfunction "40_40") (pintype "passive"))
    )
    (net (code "38") (name "/TRISTATE_STEPPERS") (class "Default")
      (node (ref "IC18") (pin "1") (pinfunction "OE_1") (pintype "input"))
    )
    (net (code "39") (name "/V+") (class "Default")
      (node (ref "U3") (pin "16") (pinfunction "V+_16") (pintype "power_in"))
    )
    (net (code "40") (name "/VDD_ADC") (class "Default")
      (node (ref "P9") (pin "32") (pinfunction "32_32") (pintype "passive"))
      (node (ref "R13") (pin "2") (pinfunction "2_2") (pintype "passive"))
    )
    (net (code "41") (name "/VDD_IN") (class "Default")
      (node (ref "12..24V") (pin "TP") (pinfunction "TP_TP") (pintype "input"))
      (node (ref "C11") (pin "1") (pinfunction "1_1") (pintype "passive"))
      (node (ref "C16") (pin "1") (pinfunction "1_1") (pintype "passive"))
      (node (ref "C20") (pin "2") (pinfunction "2_2") (pintype "passive"))
      (node (ref "C22") (pin "2") (pinfunction "2_2") (pintype "passive"))
      (node (ref "C27") (pin "1") (pinfunction "1_1") (pintype "passive"))
      (node (ref "C28") (pin "2") (pinfunction "2_2") (pintype "passive"))
      (node (ref "C31") (pin "1") (pinfunction "1_1") (pintype "passive"))
      (node (ref "C35") (pin "2") (pinfunction "2_2") (pintype "passive"))
      (node (ref "C4") (pin "1") (pinfunction "1_1") (pintype "passive"))
      (node (ref "C6") (pin "1") (pinfunction "1_1") (pintype "passive"))
      (node (ref "D1") (pin "C") (pinfunction "C_C") (pintype "passive"))
      (node (ref "D3") (pin "C") (pinfunction "C_C") (pintype "passive"))
      (node (ref "D5") (pin "C") (pinfunction "C_C") (pintype "passive"))
      (node (ref "F1") (pin "P$3") (pinfunction "2_P$3") (pintype "passive"))
      (node (ref "F1") (pin "P$4") (pinfunction "2_P$4") (pintype "passive"))
      (node (ref "IC1") (pin "16") (pinfunction "VS_16") (pintype "bidirectional"))
      (node (ref "IC1") (pin "30") (pinfunction "VSA_30") (pintype "bidirectional"))
      (node (ref "IC1") (pin "31") (pinfunction "VS_31") (pintype "bidirectional"))
      (node (ref "IC2") (pin "16") (pinfunction "VS_16") (pintype "bidirectional"))
      (node (ref "IC2") (pin "30") (pinfunction "VSA_30") (pintype "bidirectional"))
      (node (ref "IC2") (pin "31") (pinfunction "VS_31") (pintype "bidirectional"))
      (node (ref "R14") (pin "2") (pinfunction "2_2") (pintype "passive"))
      (node (ref "R15") (pin "2") (pinfunction "2_2") (pintype "passive"))
      (node (ref "R45") (pin "1") (pinfunction "1_1") (pintype "passive"))
      (node (ref "R55") (pin "2") (pinfunction "2_2") (pintype "passive"))
      (node (ref "R57") (pin "2") (pinfunction "2_2") (pintype "passive"))
      (node (ref "X21") (pin "1") (pinfunction "1_1") (pintype "passive"))
      (node (ref "X3") (pin "1") (pinfunction "1_1") (pintype "passive"))
    )
    (net (code "42") (name "/VIN") (class "Default")
      (node (ref "F1") (pin "P$1") (pinfunction "1_P$1") (pintype "passive"))
      (node (ref "F1") (pin "P$2") (pinfunction "1_P$2") (pintype "passive"))
      (node (ref "LED8") (pin "A") (pinfunction "A_A") (pintype "passive"))
      (node (ref "X2") (pin "3") (pinfunction "1_3") (pintype "passive"))
      (node (ref "X2") (pin "4") (pinfunction "1_4") (pintype "passive"))
    )
    (net (code "43") (name "GND") (class "Default")
      (node (ref "C11") (pin "2") (pinfunction "2_2") (pintype "passive"))
      (node (ref "C12") (pin "2") (pinfunction "2_2") (pintype "passive"))
      (node (ref "C13") (pin "2") (pinfunction "2_2") (pintype "passive"))
      (node (ref "C16") (pin "2") (pinfunction "2_2") (pintype "passive"))
      (node (ref "C17") (pin "2") (pinfunction "2_2") (pintype "passive"))
      (node (ref "C18") (pin "2") (pinfunction "2_2") (pintype "passive"))
      (node (ref "C2") (pin "2") (pinfunction "2_2") (pintype "passive"))
      (node (ref "C20") (pin "1") (pinfunction "1_1") (pintype "passive"))
      (node (ref "C21") (pin "1") (pinfunction "1_1") (pintype "passive"))
      (node (ref "C23") (pin "2") (pinfunction "2_2") (pintype "passive"))
      (node (ref "C27") (pin "2") (pinfunction "2_2") (pintype "passive"))
      (node (ref "C28") (pin "1") (pinfunction "1_1") (pintype "passive"))
      (node (ref "C31") (pin "2") (pinfunction "2_2") (pintype "passive"))
      (node (ref "C33") (pin "1") (pinfunction "1_1") (pintype "passive"))
      (node (ref "C4") (pin "2") (pinfunction "2_2") (pintype "passive"))
      (node (ref "C41") (pin "2") (pinfunction "2_2") (pintype "passive"))
      (node (ref "C5") (pin "2") (pinfunction "2_2") (pintype "passive"))
      (node (ref "C57") (pin "2") (pinfunction "2_2") (pintype "passive"))
      (node (ref "C59") (pin "2") (pinfunction "2_2") (pintype "passive"))
      (node (ref "C6") (pin "2") (pinfunction "2_2") (pintype "passive"))
      (node (ref "C71") (pin "2") (pinfunction "2_2") (pintype "passive"))
      (node (ref "C72") (pin "2") (pinfunction "2_2") (pintype "passive"))
      (node (ref "C76") (pin "2") (pinfunction "2_2") (pintype "passive"))
      (node (ref "C77") (pin "2") (pinfunction "2_2") (pintype "passive"))
      (node (ref "C85") (pin "2") (pinfunction "2_2") (pintype "passive"))
      (node (ref "C86") (pin "2") (pinfunction "2_2") (pintype "passive"))
      (node (ref "D5") (pin "A") (pinfunction "A_A") (pintype "passive"))
      (node (ref "IC1") (pin "1") (pinfunction "CLK_1") (pintype "bidirectional"))
      (node (ref "IC1") (pin "10") (pinfunction "SPI_MODE_10") (pintype "bidirectional"))
      (node (ref "IC1") (pin "11") (pinfunction "GND_11") (pintype "bidirectional"))
      (node (ref "IC1") (pin "12") (pinfunction "GND_12") (pintype "bidirectional"))
      (node (ref "IC1") (pin "24") (pinfunction "GNDA_24") (pintype "bidirectional"))
      (node (ref "IC1") (pin "35") (pinfunction "GND_35") (pintype "bidirectional"))
      (node (ref "IC1") (pin "36") (pinfunction "TST_MODE_36") (pintype "bidirectional"))
      (node (ref "IC1") (pin "TP") (pinfunction "GND_TP") (pintype "bidirectional"))
      (node (ref "IC18") (pin "3") (pinfunction "GND_3") (pintype "power_in"))
      (node (ref "IC2") (pin "1") (pinfunction "CLK_1") (pintype "bidirectional"))
      (node (ref "IC2") (pin "10") (pinfunction "SPI_MODE_10") (pintype "bidirectional"))
      (node (ref "IC2") (pin "11") (pinfunction "GND_11") (pintype "bidirectional"))
      (node (ref "IC2") (pin "12") (pinfunction "GND_12") (pintype "bidirectional"))
      (node (ref "IC2") (pin "24") (pinfunction "GNDA_24") (pintype "bidirectional"))
      (node (ref "IC2") (pin "35") (pinfunction "GND_35") (pintype "bidirectional"))
      (node (ref "IC2") (pin "36") (pinfunction "TST_MODE_36") (pintype "bidirectional"))
      (node (ref "IC2") (pin "TP") (pinfunction "GND_TP") (pintype "bidirectional"))
      (node (ref "IC3") (pin "3") (pinfunction "GND_3") (pintype "power_in"))
      (node (ref "IC4") (pin "3") (pinfunction "GND_3") (pintype "power_in"))
      (node (ref "IC8") (pin "3") (pinfunction "GND_3") (pintype "power_in"))
      (node (ref "IC9") (pin "3") (pinfunction "GND_3") (pintype "power_in"))
      (node (ref "P8") (pin "1") (pinfunction "1_1") (pintype "passive"))
      (node (ref "P8") (pin "2") (pinfunction "2_2") (pintype "passive"))
      (node (ref "P9") (pin "1") (pinfunction "1_1") (pintype "passive"))
      (node (ref "P9") (pin "2") (pinfunction "2_2") (pintype "passive"))
      (node (ref "P9") (pin "43") (pinfunction "43_43") (pintype "passive"))
      (node (ref "P9") (pin "44") (pinfunction "44_44") (pintype "passive"))
      (node (ref "P9") (pin "45") (pinfunction "45_45") (pintype "passive"))
      (node (ref "P9") (pin "46") (pinfunction "46_46") (pintype "passive"))
      (node (ref "Q2") (pin "1") (pinfunction "S_1") (pintype "passive"))
      (node (ref "Q2") (pin "2") (pinfunction "S_2") (pintype "passive"))
      (node (ref "Q2") (pin "3") (pinfunction "S_3") (pintype "passive"))
      (node (ref "Q3") (pin "1") (pinfunction "S_1") (pintype "passive"))
      (node (ref "Q3") (pin "2") (pinfunction "S_2") (pintype "passive"))
      (node (ref "Q3") (pin "3") (pinfunction "S_3") (pintype "passive"))
      (node (ref "R1") (pin "1") (pinfunction "1_1") (pintype "passive"))
      (node (ref "R2") (pin "1") (pinfunction "1_1") (pintype "passive"))
      (node (ref "R3") (pin "1") (pinfunction "1_1") (pintype "passive"))
      (node (ref "R4") (pin "1") (pinfunction "1_1") (pintype "passive"))
      (node (ref "R47") (pin "1") (pinfunction "1_1") (pintype "passive"))
      (node (ref "R48") (pin "1") (pinfunction "1_1") (pintype "passive"))
      (node (ref "U1") (pin "13") (pinfunction "~{OE}_13") (pintype "input"))
      (node (ref "U1") (pin "8") (pinfunction "GND_8") (pintype "passive"))
      (node (ref "U11") (pin "14") (pinfunction "VSS_14") (pintype "passive"))
      (node (ref "U11") (pin "24") (pinfunction "A5_24") (pintype "input"))
      (node (ref "U18") (pin "2") (pinfunction "A1_2") (pintype "input"))
      (node (ref "U18") (pin "4") (pinfunction "GND_4") (pintype "power_in"))
      (node (ref "U2") (pin "13") (pinfunction "~{OE}_13") (pintype "input"))
      (node (ref "U2") (pin "8") (pinfunction "GND_8") (pintype "passive"))
      (node (ref "X11") (pin "1") (pinfunction "S_1") (pintype "passive"))
      (node (ref "X2") (pin "1") (pinfunction "1_1") (pintype "passive"))
      (node (ref "X2") (pin "2") (pinfunction "1_2") (pintype "passive"))
    )
    (net (code "44") (name "Net-(C76-Pad1)") (class "Default")
      (node (ref "C76") (pin "1") (pinfunction "1_1") (pintype "passive"))
      (node (ref "R37") (pin "1") (pinfunction "1_1") (pintype "passive"))
      (node (ref "R6") (pin "2") (pinfunction "2_2") (pintype "passive"))
    )
    (net (code "45") (name "Net-(C77-Pad1)") (class "Default")
      (node (ref "C77") (pin "1") (pinfunction "1_1") (pintype "passive"))
      (node (ref "R41") (pin "1") (pinfunction "1_1") (pintype "passive"))
      (node (ref "R49") (pin "2") (pinfunction "2_2") (pintype "passive"))
    )
    (net (code "46") (name "Net-(IC1-5VOUT)") (class "Default")
      (node (ref "C21") (pin "2") (pinfunction "2_2") (pintype "passive"))
      (node (ref "IC1") (pin "25") (pinfunction "5VOUT_25") (pintype "bidirectional"))
      (node (ref "R53") (pin "1") (pinfunction "1_1") (pintype "passive"))
    )
    (net (code "47") (name "Net-(IC1-AIN_IREF)") (class "Default")
      (node (ref "C12") (pin "1") (pinfunction "1_1") (pintype "passive"))
      (node (ref "IC1") (pin "23") (pinfunction "AIN_IREF_23") (pintype "bidirectional"))
      (node (ref "R49") (pin "1") (pinfunction "1_1") (pintype "passive"))
    )
    (net (code "48") (name "Net-(IC1-BRA)") (class "Default")
      (node (ref "IC1") (pin "33") (pinfunction "BRA_33") (pintype "bidirectional"))
      (node (ref "R2") (pin "2") (pinfunction "2_2") (pintype "passive"))
    )
    (net (code "49") (name "Net-(IC1-BRB)") (class "Default")
      (node (ref "IC1") (pin "14") (pinfunction "BRB_14") (pintype "bidirectional"))
      (node (ref "R1") (pin "2") (pinfunction "2_2") (pintype "passive"))
    )
    (net (code "50") (name "Net-(IC1-CPI)") (class "Default")
      (node (ref "C1") (pin "1") (pinfunction "1_1") (pintype "passive"))
      (node (ref "IC1") (pin "28") (pinfunction "CPI_28") (pintype "bidirectional"))
    )
    (net (code "51") (name "Net-(IC1-CPO)") (class "Default")
      (node (ref "C1") (pin "2") (pinfunction "2_2") (pintype "passive"))
      (node (ref "IC1") (pin "27") (pinfunction "CPO_27") (pintype "bidirectional"))
    )
    (net (code "52") (name "Net-(IC1-ENCA_DCIN_CFG5)") (class "Default")
      (node (ref "IC1") (pin "19") (pinfunction "ENCA_DCIN_CFG5_19") (pintype "bidirectional"))
      (node (ref "U1") (pin "1") (pinfunction "QB_1") (pintype "output"))
    )
    (net (code "53") (name "Net-(IC1-ENCB_DCEN_CFG4)") (class "Default")
      (node (ref "IC1") (pin "18") (pinfunction "ENCB_DCEN_CFG4_18") (pintype "bidirectional"))
      (node (ref "U1") (pin "2") (pinfunction "QC_2") (pintype "output"))
    )
    (net (code "54") (name "Net-(IC1-OA1)") (class "Default")
      (node (ref "IC1") (pin "34") (pinfunction "OA1_34") (pintype "bidirectional"))
      (node (ref "X14") (pin "2") (pinfunction "S_2") (pintype "passive"))
    )
    (net (code "55") (name "Net-(IC1-OA2)") (class "Default")
      (node (ref "IC1") (pin "32") (pinfunction "OA2_32") (pintype "bidirectional"))
      (node (ref "X14") (pin "1") (pinfunction "S_1") (pintype "passive"))
    )
    (net (code "56") (name "Net-(IC1-OB1)") (class "Default")
      (node (ref "IC1") (pin "13") (pinfunction "OB1_13") (pintype "bidirectional"))
      (node (ref "X14") (pin "3") (pinfunction "S_3") (pintype "passive"))
    )
    (net (code "57") (name "Net-(IC1-OB2)") (class "Default")
      (node (ref "IC1") (pin "15") (pinfunction "OB2_15") (pintype "bidirectional"))
      (node (ref "X14") (pin "4") (pinfunction "S_4") (pintype "passive"))
    )
    (net (code "58") (name "Net-(IC1-SCK_CFG2)") (class "Default")
      (node (ref "IC1") (pin "3") (pinfunction "SCK_CFG2_3") (pintype "bidirectional"))
      (node (ref "IC3") (pin "4") (pinfunction "O_4") (pintype "output"))
    )
    (net (code "59") (name "Net-(IC1-SDI_NAI_CFG1)") (class "Default")
      (node (ref "IC1") (pin "4") (pinfunction "SDI_NAI_CFG1_4") (pintype "bidirectional"))
      (node (ref "IC4") (pin "4") (pinfunction "O_4") (pintype "output"))
    )
    (net (code "60") (name "Net-(IC1-SDO_NAO_CFG0)") (class "Default")
      (node (ref "IC1") (pin "5") (pinfunction "SDO_NAO_CFG0_5") (pintype "bidirectional"))
      (node (ref "U1") (pin "3") (pinfunction "QD_3") (pintype "output"))
    )
    (net (code "61") (name "Net-(IC1-VCC)") (class "Default")
      (node (ref "C71") (pin "1") (pinfunction "1_1") (pintype "passive"))
      (node (ref "IC1") (pin "26") (pinfunction "VCC_26") (pintype "bidirectional"))
      (node (ref "R53") (pin "2") (pinfunction "2_2") (pintype "passive"))
    )
    (net (code "62") (name "Net-(IC1-VCP)") (class "Default")
      (node (ref "C22") (pin "1") (pinfunction "1_1") (pintype "passive"))
      (node (ref "IC1") (pin "29") (pinfunction "VCP_29") (pintype "bidirectional"))
    )
    (net (code "63") (name "Net-(IC2-5VOUT)") (class "Default")
      (node (ref "C33") (pin "2") (pinfunction "2_2") (pintype "passive"))
      (node (ref "IC2") (pin "25") (pinfunction "5VOUT_25") (pintype "bidirectional"))
      (node (ref "R59") (pin "1") (pinfunction "1_1") (pintype "passive"))
    )
    (net (code "64") (name "Net-(IC2-AIN_IREF)") (class "Default")
      (node (ref "C18") (pin "1") (pinfunction "1_1") (pintype "passive"))
      (node (ref "IC2") (pin "23") (pinfunction "AIN_IREF_23") (pintype "bidirectional"))
      (node (ref "R6") (pin "1") (pinfunction "1_1") (pintype "passive"))
    )
    (net (code "65") (name "Net-(IC2-BRA)") (class "Default")
      (node (ref "IC2") (pin "33") (pinfunction "BRA_33") (pintype "bidirectional"))
      (node (ref "R4") (pin "2") (pinfunction "2_2") (pintype "passive"))
    )
    (net (code "66") (name "Net-(IC2-BRB)") (class "Default")
      (node (ref "IC2") (pin "14") (pinfunction "BRB_14") (pintype "bidirectional"))
      (node (ref "R3") (pin "2") (pinfunction "2_2") (pintype "passive"))
    )
    (net (code "67") (name "Net-(IC2-CPI)") (class "Default")
      (node (ref "C3") (pin "1") (pinfunction "1_1") (pintype "passive"))
      (node (ref "IC2") (pin "28") (pinfunction "CPI_28") (pintype "bidirectional"))
    )
    (net (code "68") (name "Net-(IC2-CPO)") (class "Default")
      (node (ref "C3") (pin "2") (pinfunction "2_2") (pintype "passive"))
      (node (ref "IC2") (pin "27") (pinfunction "CPO_27") (pintype "bidirectional"))
    )
    (net (code "69") (name "Net-(IC2-ENCA_DCIN_CFG5)") (class "Default")
      (node (ref "IC2") (pin "19") (pinfunction "ENCA_DCIN_CFG5_19") (pintype "bidirectional"))
      (node (ref "U2") (pin "1") (pinfunction "QB_1") (pintype "output"))
    )
    (net (code "70") (name "Net-(IC2-ENCB_DCEN_CFG4)") (class "Default")
      (node (ref "IC2") (pin "18") (pinfunction "ENCB_DCEN_CFG4_18") (pintype "bidirectional"))
      (node (ref "U2") (pin "2") (pinfunction "QC_2") (pintype "output"))
    )
    (net (code "71") (name "Net-(IC2-OA1)") (class "Default")
      (node (ref "IC2") (pin "34") (pinfunction "OA1_34") (pintype "bidirectional"))
      (node (ref "X15") (pin "2") (pinfunction "S_2") (pintype "passive"))
    )
    (net (code "72") (name "Net-(IC2-OA2)") (class "Default")
      (node (ref "IC2") (pin "32") (pinfunction "OA2_32") (pintype "bidirectional"))
      (node (ref "X15") (pin "1") (pinfunction "S_1") (pintype "passive"))
    )
    (net (code "73") (name "Net-(IC2-OB1)") (class "Default")
      (node (ref "IC2") (pin "13") (pinfunction "OB1_13") (pintype "bidirectional"))
      (node (ref "X15") (pin "3") (pinfunction "S_3") (pintype "passive"))
    )
    (net (code "74") (name "Net-(IC2-OB2)") (class "Default")
      (node (ref "IC2") (pin "15") (pinfunction "OB2_15") (pintype "bidirectional"))
      (node (ref "X15") (pin "4") (pinfunction "S_4") (pintype "passive"))
    )
    (net (code "75") (name "Net-(IC2-SCK_CFG2)") (class "Default")
      (node (ref "IC2") (pin "3") (pinfunction "SCK_CFG2_3") (pintype "bidirectional"))
      (node (ref "IC8") (pin "4") (pinfunction "O_4") (pintype "output"))
    )
    (net (code "76") (name "Net-(IC2-SDI_NAI_CFG1)") (class "Default")
      (node (ref "IC2") (pin "4") (pinfunction "SDI_NAI_CFG1_4") (pintype "bidirectional"))
      (node (ref "IC9") (pin "4") (pinfunction "O_4") (pintype "output"))
    )
    (net (code "77") (name "Net-(IC2-SDO_NAO_CFG0)") (class "Default")
      (node (ref "IC2") (pin "5") (pinfunction "SDO_NAO_CFG0_5") (pintype "bidirectional"))
      (node (ref "U2") (pin "3") (pinfunction "QD_3") (pintype "output"))
    )
    (net (code "78") (name "Net-(IC2-VCC)") (class "Default")
      (node (ref "C72") (pin "1") (pinfunction "1_1") (pintype "passive"))
      (node (ref "IC2") (pin "26") (pinfunction "VCC_26") (pintype "bidirectional"))
      (node (ref "R59") (pin "2") (pinfunction "2_2") (pintype "passive"))
    )
    (net (code "79") (name "Net-(IC2-VCP)") (class "Default")
      (node (ref "C35") (pin "1") (pinfunction "1_1") (pintype "passive"))
      (node (ref "IC2") (pin "29") (pinfunction "VCP_29") (pintype "bidirectional"))
    )
    (net (code "80") (name "Net-(IC3A-I)") (class "Default")
      (node (ref "IC3") (pin "2") (pinfunction "I_2") (pintype "input"))
      (node (ref "U1") (pin "4") (pinfunction "QE_4") (pintype "output"))
    )
    (net (code "81") (name "Net-(IC3A-OE)") (class "Default")
      (node (ref "IC3") (pin "1") (pinfunction "OE_1") (pintype "input"))
      (node (ref "U1") (pin "5") (pinfunction "QF_5") (pintype "output"))
    )
    (net (code "82") (name "Net-(IC4A-I)") (class "Default")
      (node (ref "IC4") (pin "2") (pinfunction "I_2") (pintype "input"))
      (node (ref "U1") (pin "6") (pinfunction "QG_6") (pintype "output"))
    )
    (net (code "83") (name "Net-(IC4A-OE)") (class "Default")
      (node (ref "IC4") (pin "1") (pinfunction "OE_1") (pintype "input"))
      (node (ref "U1") (pin "7") (pinfunction "QH_7") (pintype "output"))
    )
    (net (code "84") (name "Net-(IC5A-I)") (class "Default")
      (node (ref "IC5") (pin "2") (pinfunction "I_2") (pintype "input"))
      (node (ref "U2") (pin "15") (pinfunction "QA_15") (pintype "output"))
    )
    (net (code "85") (name "Net-(IC8A-I)") (class "Default")
      (node (ref "IC8") (pin "2") (pinfunction "I_2") (pintype "input"))
      (node (ref "U2") (pin "4") (pinfunction "QE_4") (pintype "output"))
    )
    (net (code "86") (name "Net-(IC8A-OE)") (class "Default")
      (node (ref "IC8") (pin "1") (pinfunction "OE_1") (pintype "input"))
      (node (ref "U2") (pin "5") (pinfunction "QF_5") (pintype "output"))
    )
    (net (code "87") (name "Net-(IC9A-I)") (class "Default")
      (node (ref "IC9") (pin "2") (pinfunction "I_2") (pintype "input"))
      (node (ref "U2") (pin "6") (pinfunction "QG_6") (pintype "output"))
    )
    (net (code "88") (name "Net-(IC9A-OE)") (class "Default")
      (node (ref "IC9") (pin "1") (pinfunction "OE_1") (pintype "input"))
      (node (ref "U2") (pin "7") (pinfunction "QH_7") (pintype "output"))
    )
    (net (code "89") (name "Net-(IC18A-I)") (class "Default")
      (node (ref "IC18") (pin "2") (pinfunction "I_2") (pintype "input"))
      (node (ref "U1") (pin "15") (pinfunction "QA_15") (pintype "output"))
    )
    (net (code "90") (name "Net-(LED1-PadA)") (class "Default")
      (node (ref "LED1") (pin "A") (pinfunction "A_A") (pintype "passive"))
      (node (ref "R14") (pin "1") (pinfunction "1_1") (pintype "passive"))
    )
    (net (code "91") (name "Net-(LED3-PadA)") (class "Default")
      (node (ref "LED3") (pin "A") (pinfunction "A_A") (pintype "passive"))
      (node (ref "R15") (pin "1") (pinfunction "1_1") (pintype "passive"))
    )
    (net (code "92") (name "Net-(LED8-PadC)") (class "Default")
      (node (ref "LED8") (pin "C") (pinfunction "C_C") (pintype "passive"))
      (node (ref "R45") (pin "2") (pinfunction "2_2") (pintype "passive"))
    )
    (net (code "93") (name "Net-(X3B-1)") (class "Default")
      (node (ref "C59") (pin "1") (pinfunction "1_1") (pintype "passive"))
      (node (ref "D1") (pin "A") (pinfunction "A_A") (pintype "passive"))
      (node (ref "LED3") (pin "C") (pinfunction "C_C") (pintype "passive"))
      (node (ref "Q3") (pin "5") (pinfunction "D_5") (pintype "passive"))
      (node (ref "Q3") (pin "6") (pinfunction "D_6") (pintype "passive"))
      (node (ref "Q3") (pin "7") (pinfunction "D_7") (pintype "passive"))
      (node (ref "Q3") (pin "8") (pinfunction "D_8") (pintype "passive"))
      (node (ref "Q3") (pin "TH") (pinfunction "D_TH") (pintype "passive"))
      (node (ref "R55") (pin "1") (pinfunction "1_1") (pintype "passive"))
      (node (ref "X3") (pin "2") (pinfunction "1_2") (pintype "passive"))
    )
    (net (code "94") (name "Net-(X8A-S)") (class "Default")
      (node (ref "C26") (pin "2") (pinfunction "2_2") (pintype "passive"))
      (node (ref "X8") (pin "1") (pinfunction "S_1") (pintype "passive"))
    )
    (net (code "95") (name "Net-(X8B-S)") (class "Default")
      (node (ref "R13") (pin "1") (pinfunction "1_1") (pintype "passive"))
      (node (ref "R38") (pin "1") (pinfunction "1_1") (pintype "passive"))
      (node (ref "X8") (pin "2") (pinfunction "S_2") (pintype "passive"))
    )
    (net (code "96") (name "Net-(X21B-1)") (class "Default")
      (node (ref "C57") (pin "1") (pinfunction "1_1") (pintype "passive"))
      (node (ref "D3") (pin "A") (pinfunction "A_A") (pintype "passive"))
      (node (ref "LED1") (pin "C") (pinfunction "C_C") (pintype "passive"))
      (node (ref "Q2") (pin "5") (pinfunction "D_5") (pintype "passive"))
      (node (ref "Q2") (pin "6") (pinfunction "D_6") (pintype "passive"))
      (node (ref "Q2") (pin "7") (pinfunction "D_7") (pintype "passive"))
      (node (ref "Q2") (pin "8") (pinfunction "D_8") (pintype "passive"))
      (node (ref "Q2") (pin "TH") (pinfunction "D_TH") (pintype "passive"))
      (node (ref "R57") (pin "1") (pinfunction "1_1") (pintype "passive"))
      (node (ref "X21") (pin "2") (pinfunction "1_2") (pintype "passive"))
    )
    (net (code "97") (name "unconnected-(C46-Pad2)") (class "Default")
      (node (ref "C46") (pin "2") (pinfunction "2_2") (pintype "passive"))
    )
    (net (code "98") (name "unconnected-(IC1-CSN_CFG3-Pad2)") (class "Default")
      (node (ref "IC1") (pin "2") (pinfunction "CSN_CFG3_2") (pintype "bidirectional"))
    )
    (net (code "99") (name "unconnected-(IC1-ENCN_DCO-Pad17)") (class "Default")
      (node (ref "IC1") (pin "17") (pinfunction "ENCN_DCO_17") (pintype "bidirectional"))
    )
    (net (code "100") (name "unconnected-(IC1-SD_MODE-Pad9)") (class "Default")
      (node (ref "IC1") (pin "9") (pinfunction "SD_MODE_9") (pintype "bidirectional"))
    )
    (net (code "101") (name "unconnected-(IC1-SWP_DIAG1-Pad21)") (class "Default")
      (node (ref "IC1") (pin "21") (pinfunction "SWP_DIAG1_21") (pintype "bidirectional"))
    )
    (net (code "102") (name "unconnected-(IC2-CSN_CFG3-Pad2)") (class "Default")
      (node (ref "IC2") (pin "2") (pinfunction "CSN_CFG3_2") (pintype "bidirectional"))
    )
    (net (code "103") (name "unconnected-(IC2-ENCN_DCO-Pad17)") (class "Default")
      (node (ref "IC2") (pin "17") (pinfunction "ENCN_DCO_17") (pintype "bidirectional"))
    )
    (net (code "104") (name "unconnected-(IC2-SD_MODE-Pad9)") (class "Default")
      (node (ref "IC2") (pin "9") (pinfunction "SD_MODE_9") (pintype "bidirectional"))
    )
    (net (code "105") (name "unconnected-(IC2-SWP_DIAG1-Pad21)") (class "Default")
      (node (ref "IC2") (pin "21") (pinfunction "SWP_DIAG1_21") (pintype "bidirectional"))
    )
    (net (code "106") (name "unconnected-(IC5A-OE-Pad1)") (class "Default")
      (node (ref "IC5") (pin "1") (pinfunction "OE_1") (pintype "input"))
    )
    (net (code "107") (name "unconnected-(J1A-S-Pad1)") (class "Default")
      (node (ref "J1") (pin "1") (pinfunction "S_1") (pintype "passive"))
    )
    (net (code "108") (name "unconnected-(J1B-S-Pad2)") (class "Default")
      (node (ref "J1") (pin "2") (pinfunction "S_2") (pintype "passive"))
    )
    (net (code "109") (name "unconnected-(J1C-S-Pad3)") (class "Default")
      (node (ref "J1") (pin "3") (pinfunction "S_3") (pintype "passive"))
    )
    (net (code "110") (name "unconnected-(P8-Pad3)") (class "Default")
      (node (ref "P8") (pin "3") (pinfunction "3_3") (pintype "passive"))
    )
    (net (code "111") (name "unconnected-(P8-Pad4)") (class "Default")
      (node (ref "P8") (pin "4") (pinfunction "4_4") (pintype "passive"))
    )
    (net (code "112") (name "unconnected-(P8-Pad5)") (class "Default")
      (node (ref "P8") (pin "5") (pinfunction "5_5") (pintype "passive"))
    )
    (net (code "113") (name "unconnected-(P8-Pad6)") (class "Default")
      (node (ref "P8") (pin "6") (pinfunction "6_6") (pintype "passive"))
    )
    (net (code "114") (name "unconnected-(P8-Pad8)") (class "Default")
      (node (ref "P8") (pin "8") (pinfunction "8_8") (pintype "passive"))
    )
    (net (code "115") (name "unconnected-(P8-Pad9)") (class "Default")
      (node (ref "P8") (pin "9") (pinfunction "9_9") (pintype "passive"))
    )
    (net (code "116") (name "unconnected-(P8-Pad10)") (class "Default")
      (node (ref "P8") (pin "10") (pinfunction "10_10") (pintype "passive"))
    )
    (net (code "117") (name "unconnected-(P8-Pad11)") (class "Default")
      (node (ref "P8") (pin "11") (pinfunction "11_11") (pintype "passive"))
    )
    (net (code "118") (name "unconnected-(P8-Pad12)") (class "Default")
      (node (ref "P8") (pin "12") (pinfunction "12_12") (pintype "passive"))
    )
    (net (code "119") (name "unconnected-(P8-Pad13)") (class "Default")
      (node (ref "P8") (pin "13") (pinfunction "13_13") (pintype "passive"))
    )
    (net (code "120") (name "unconnected-(P8-Pad14)") (class "Default")
      (node (ref "P8") (pin "14") (pinfunction "14_14") (pintype "passive"))
    )
    (net (code "121") (name "unconnected-(P8-Pad15)") (class "Default")
      (node (ref "P8") (pin "15") (pinfunction "15_15") (pintype "passive"))
    )
    (net (code "122") (name "unconnected-(P8-Pad16)") (class "Default")
      (node (ref "P8") (pin "16") (pinfunction "16_16") (pintype "passive"))
    )
    (net (code "123") (name "unconnected-(P8-Pad17)") (class "Default")
      (node (ref "P8") (pin "17") (pinfunction "17_17") (pintype "passive"))
    )
    (net (code "124") (name "unconnected-(P8-Pad18)") (class "Default")
      (node (ref "P8") (pin "18") (pinfunction "18_18") (pintype "passive"))
    )
    (net (code "125") (name "unconnected-(P8-Pad19)") (class "Default")
      (node (ref "P8") (pin "19") (pinfunction "19_19") (pintype "passive"))
    )
    (net (code "126") (name "unconnected-(P8-Pad20)") (class "Default")
      (node (ref "P8") (pin "20") (pinfunction "20_20") (pintype "passive"))
    )
    (net (code "127") (name "unconnected-(P8-Pad21)") (class "Default")
      (node (ref "P8") (pin "21") (pinfunction "21_21") (pintype "passive"))
    )
    (net (code "128") (name "unconnected-(P8-Pad22)") (class "Default")
      (node (ref "P8") (pin "22") (pinfunction "22_22") (pintype "passive"))
    )
    (net (code "129") (name "unconnected-(P8-Pad23)") (class "Default")
      (node (ref "P8") (pin "23") (pinfunction "23_23") (pintype "passive"))
    )
    (net (code "130") (name "unconnected-(P8-Pad24)") (class "Default")
      (node (ref "P8") (pin "24") (pinfunction "24_24") (pintype "passive"))
    )
    (net (code "131") (name "unconnected-(P8-Pad25)") (class "Default")
      (node (ref "P8") (pin "25") (pinfunction "25_25") (pintype "passive"))
    )
    (net (code "132") (name "unconnected-(P8-Pad26)") (class "Default")
      (node (ref "P8") (pin "26") (pinfunction "26_26") (pintype "passive"))
    )
    (net (code "133") (name "unconnected-(P8-Pad27)") (class "Default")
      (node (ref "P8") (pin "27") (pinfunction "27_27") (pintype "passive"))
    )
    (net (code "134") (name "unconnected-(P8-Pad28)") (class "Default")
      (node (ref "P8") (pin "28") (pinfunction "28_28") (pintype "passive"))
    )
    (net (code "135") (name "unconnected-(P8-Pad29)") (class "Default")
      (node (ref "P8") (pin "29") (pinfunction "29_29") (pintype "passive"))
    )
    (net (code "136") (name "unconnected-(P8-Pad30)") (class "Default")
      (node (ref "P8") (pin "30") (pinfunction "30_30") (pintype "passive"))
    )
    (net (code "137") (name "unconnected-(P8-Pad31)") (class "Default")
      (node (ref "P8") (pin "31") (pinfunction "31_31") (pintype "passive"))
    )
    (net (code "138") (name "unconnected-(P8-Pad32)") (class "Default")
      (node (ref "P8") (pin "32") (pinfunction "32_32") (pintype "passive"))
    )
    (net (code "139") (name "unconnected-(P8-Pad33)") (class "Default")
      (node (ref "P8") (pin "33") (pinfunction "33_33") (pintype "passive"))
    )
    (net (code "140") (name "unconnected-(P8-Pad34)") (class "Default")
      (node (ref "P8") (pin "34") (pinfunction "34_34") (pintype "passive"))
    )
    (net (code "141") (name "unconnected-(P8-Pad35)") (class "Default")
      (node (ref "P8") (pin "35") (pinfunction "35_35") (pintype "passive"))
    )
    (net (code "142") (name "unconnected-(P8-Pad36)") (class "Default")
      (node (ref "P8") (pin "36") (pinfunction "36_36") (pintype "passive"))
    )
    (net (code "143") (name "unconnected-(P8-Pad37)") (class "Default")
      (node (ref "P8") (pin "37") (pinfunction "37_37") (pintype "passive"))
    )
    (net (code "144") (name "unconnected-(P8-Pad38)") (class "Default")
      (node (ref "P8") (pin "38") (pinfunction "38_38") (pintype "passive"))
    )
    (net (code "145") (name "unconnected-(P8-Pad39)") (class "Default")
      (node (ref "P8") (pin "39") (pinfunction "39_39") (pintype "passive"))
    )
    (net (code "146") (name "unconnected-(P8-Pad40)") (class "Default")
      (node (ref "P8") (pin "40") (pinfunction "40_40") (pintype "passive"))
    )
    (net (code "147") (name "unconnected-(P8-Pad41)") (class "Default")
      (node (ref "P8") (pin "41") (pinfunction "41_41") (pintype "passive"))
    )
    (net (code "148") (name "unconnected-(P8-Pad42)") (class "Default")
      (node (ref "P8") (pin "42") (pinfunction "42_42") (pintype "passive"))
    )
    (net (code "149") (name "unconnected-(P8-Pad43)") (class "Default")
      (node (ref "P8") (pin "43") (pinfunction "43_43") (pintype "passive"))
    )
    (net (code "150") (name "unconnected-(P8-Pad44)") (class "Default")
      (node (ref "P8") (pin "44") (pinfunction "44_44") (pintype "passive"))
    )
    (net (code "151") (name "unconnected-(P8-Pad45)") (class "Default")
      (node (ref "P8") (pin "45") (pinfunction "45_45") (pintype "passive"))
    )
    (net (code "152") (name "unconnected-(P8-Pad46)") (class "Default")
      (node (ref "P8") (pin "46") (pinfunction "46_46") (pintype "passive"))
    )
    (net (code "153") (name "unconnected-(P9-Pad7)") (class "Default")
      (node (ref "P9") (pin "7") (pinfunction "7_7") (pintype "passive"))
    )
    (net (code "154") (name "unconnected-(P9-Pad8)") (class "Default")
      (node (ref "P9") (pin "8") (pinfunction "8_8") (pintype "passive"))
    )
    (net (code "155") (name "unconnected-(P9-Pad9)") (class "Default")
      (node (ref "P9") (pin "9") (pinfunction "9_9") (pintype "passive"))
    )
    (net (code "156") (name "unconnected-(P9-Pad10)") (class "Default")
      (node (ref "P9") (pin "10") (pinfunction "10_10") (pintype "passive"))
    )
    (net (code "157") (name "unconnected-(P9-Pad11)") (class "Default")
      (node (ref "P9") (pin "11") (pinfunction "11_11") (pintype "passive"))
    )
    (net (code "158") (name "unconnected-(P9-Pad12)") (class "Default")
      (node (ref "P9") (pin "12") (pinfunction "12_12") (pintype "passive"))
    )
    (net (code "159") (name "unconnected-(P9-Pad13)") (class "Default")
      (node (ref "P9") (pin "13") (pinfunction "13_13") (pintype "passive"))
    )
    (net (code "160") (name "unconnected-(P9-Pad14)") (class "Default")
      (node (ref "P9") (pin "14") (pinfunction "14_14") (pintype "passive"))
    )
    (net (code "161") (name "unconnected-(P9-Pad16)") (class "Default")
      (node (ref "P9") (pin "16") (pinfunction "16_16") (pintype "passive"))
    )
    (net (code "162") (name "unconnected-(P9-Pad18)") (class "Default")
      (node (ref "P9") (pin "18") (pinfunction "18_18") (pintype "passive"))
    )
    (net (code "163") (name "unconnected-(P9-Pad22)") (class "Default")
      (node (ref "P9") (pin "22") (pinfunction "22_22") (pintype "passive"))
    )
    (net (code "164") (name "unconnected-(P9-Pad23)") (class "Default")
      (node (ref "P9") (pin "23") (pinfunction "23_23") (pintype "passive"))
    )
    (net (code "165") (name "unconnected-(P9-Pad24)") (class "Default")
      (node (ref "P9") (pin "24") (pinfunction "24_24") (pintype "passive"))
    )
    (net (code "166") (name "unconnected-(P9-Pad25)") (class "Default")
      (node (ref "P9") (pin "25") (pinfunction "25_25") (pintype "passive"))
    )
    (net (code "167") (name "unconnected-(P9-Pad28)") (class "Default")
      (node (ref "P9") (pin "28") (pinfunction "28_28") (pintype "passive"))
    )
    (net (code "168") (name "unconnected-(P9-Pad29)") (class "Default")
      (node (ref "P9") (pin "29") (pinfunction "29_29") (pintype "passive"))
    )
    (net (code "169") (name "unconnected-(P9-Pad33)") (class "Default")
      (node (ref "P9") (pin "33") (pinfunction "33_33") (pintype "passive"))
    )
    (net (code "170") (name "unconnected-(P9-Pad34)") (class "Default")
      (node (ref "P9") (pin "34") (pinfunction "34_34") (pintype "passive"))
    )
    (net (code "171") (name "unconnected-(P9-Pad35)") (class "Default")
      (node (ref "P9") (pin "35") (pinfunction "35_35") (pintype "passive"))
    )
    (net (code "172") (name "unconnected-(P9-Pad36)") (class "Default")
      (node (ref "P9") (pin "36") (pinfunction "36_36") (pintype "passive"))
    )
    (net (code "173") (name "unconnected-(P9-Pad42)") (class "Default")
      (node (ref "P9") (pin "42") (pinfunction "42_42") (pintype "passive"))
    )
    (net (code "174") (name "unconnected-(R18-Pad1)") (class "Default")
      (node (ref "R18") (pin "1") (pinfunction "1_1") (pintype "passive"))
    )
    (net (code "175") (name "unconnected-(R18-Pad2)") (class "Default")
      (node (ref "R18") (pin "2") (pinfunction "2_2") (pintype "passive"))
    )
    (net (code "176") (name "unconnected-(R40-Pad1)") (class "Default")
      (node (ref "R40") (pin "1") (pinfunction "1_1") (pintype "passive"))
    )
    (net (code "177") (name "unconnected-(U3-COM1-Pad4)") (class "Default")
      (node (ref "U3") (pin "4") (pinfunction "COM1_4") (pintype "passive"))
    )
    (net (code "178") (name "unconnected-(U3-COM2-Pad7)") (class "Default")
      (node (ref "U3") (pin "7") (pinfunction "COM2_7") (pintype "passive"))
    )
    (net (code "179") (name "unconnected-(U3-COM3-Pad9)") (class "Default")
      (node (ref "U3") (pin "9") (pinfunction "COM3_9") (pintype "passive"))
    )
    (net (code "180") (name "unconnected-(U3-COM4-Pad12)") (class "Default")
      (node (ref "U3") (pin "12") (pinfunction "COM4_12") (pintype "passive"))
    )
    (net (code "181") (name "unconnected-(U3-GND-Pad8)") (class "Default")
      (node (ref "U3") (pin "8") (pinfunction "GND_8") (pintype "passive"))
    )
    (net (code "182") (name "unconnected-(U3-IN-Pad1)") (class "Default")
      (node (ref "U3") (pin "1") (pinfunction "IN_1") (pintype "passive"))
    )
    (net (code "183") (name "unconnected-(U3-NC1-Pad2)") (class "Default")
      (node (ref "U3") (pin "2") (pinfunction "NC1_2") (pintype "passive"))
    )
    (net (code "184") (name "unconnected-(U3-NC2-Pad5)") (class "Default")
      (node (ref "U3") (pin "5") (pinfunction "NC2_5") (pintype "passive"))
    )
    (net (code "185") (name "unconnected-(U3-NC3-Pad11)") (class "Default")
      (node (ref "U3") (pin "11") (pinfunction "NC3_11") (pintype "passive"))
    )
    (net (code "186") (name "unconnected-(U3-NC4-Pad14)") (class "Default")
      (node (ref "U3") (pin "14") (pinfunction "NC4_14") (pintype "passive"))
    )
    (net (code "187") (name "unconnected-(U3-NO1-Pad3)") (class "Default")
      (node (ref "U3") (pin "3") (pinfunction "NO1_3") (pintype "passive"))
    )
    (net (code "188") (name "unconnected-(U3-NO2-Pad6)") (class "Default")
      (node (ref "U3") (pin "6") (pinfunction "NO2_6") (pintype "passive"))
    )
    (net (code "189") (name "unconnected-(U3-NO3-Pad10)") (class "Default")
      (node (ref "U3") (pin "10") (pinfunction "NO3_10") (pintype "passive"))
    )
    (net (code "190") (name "unconnected-(U3-NO4-Pad13)") (class "Default")
      (node (ref "U3") (pin "13") (pinfunction "NO4_13") (pintype "passive"))
    )
    (net (code "191") (name "unconnected-(U3-~{EN}-Pad15)") (class "Default")
      (node (ref "U3") (pin "15") (pinfunction "~{EN}_15") (pintype "input"))
    )
    (net (code "192") (name "unconnected-(U11-EXTCLK-Pad25)") (class "Default")
      (node (ref "U11") (pin "25") (pinfunction "EXTCLK_25") (pintype "input"))
    )
    (net (code "193") (name "unconnected-(U11-LED0-Pad6)") (class "Default")
      (node (ref "U11") (pin "6") (pinfunction "LED0_6") (pintype "output"))
    )
    (net (code "194") (name "unconnected-(U11-LED1-Pad7)") (class "Default")
      (node (ref "U11") (pin "7") (pinfunction "LED1_7") (pintype "output"))
    )
    (net (code "195") (name "unconnected-(U11-LED2-Pad8)") (class "Default")
      (node (ref "U11") (pin "8") (pinfunction "LED2_8") (pintype "output"))
    )
    (net (code "196") (name "unconnected-(U11-LED4-Pad10)") (class "Default")
      (node (ref "U11") (pin "10") (pinfunction "LED4_10") (pintype "output"))
    )
    (net (code "197") (name "unconnected-(U11-LED6-Pad12)") (class "Default")
      (node (ref "U11") (pin "12") (pinfunction "LED6_12") (pintype "output"))
    )
    (net (code "198") (name "unconnected-(U11-LED13-Pad20)") (class "Default")
      (node (ref "U11") (pin "20") (pinfunction "LED13_20") (pintype "output"))
    )
    (net (code "199") (name "unconnected-(U11-LED14-Pad21)") (class "Default")
      (node (ref "U11") (pin "21") (pinfunction "LED14_21") (pintype "output"))
    )
    (net (code "200") (name "unconnected-(U11-LED15-Pad22)") (class "Default")
      (node (ref "U11") (pin "22") (pinfunction "LED15_22") (pintype "output"))
    )
    (net (code "201") (name "unconnected-(U18-~{WC}-Pad7)") (class "Default")
      (node (ref "U18") (pin "7") (pinfunction "~{WC}_7") (pintype "no_connect"))
    )
    (net (code "202") (name "unconnected-(X11B-S-Pad2)") (class "Default")
      (node (ref "X11") (pin "2") (pinfunction "S_2") (pintype "passive"))
    )
  )
)
